# FlightControllerBoard.net
KiCad netlist of a schematic drawn in EAGLE
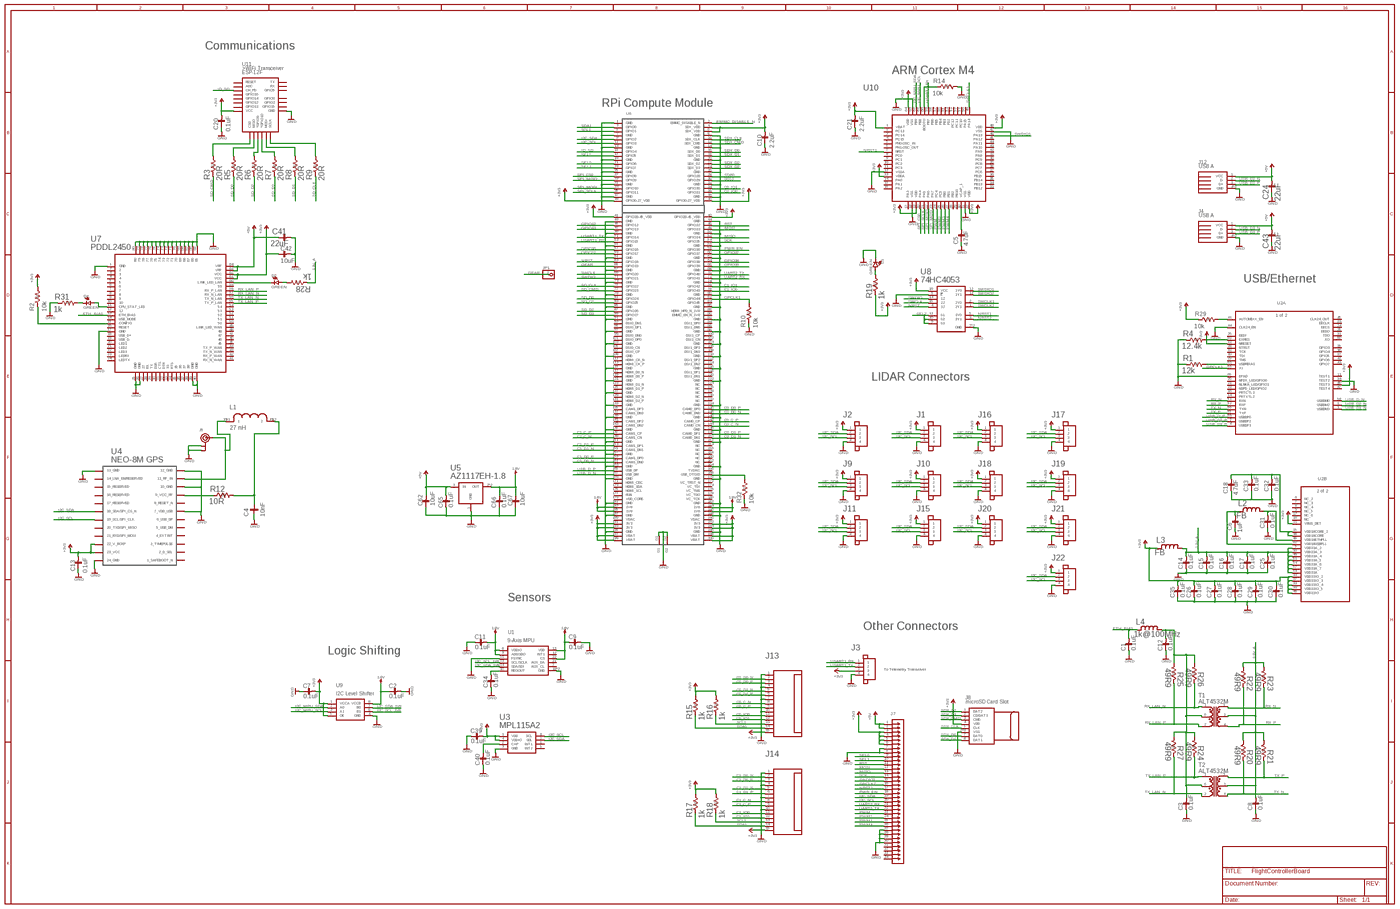
[diagram p0: schematic, sheet 1, overview]
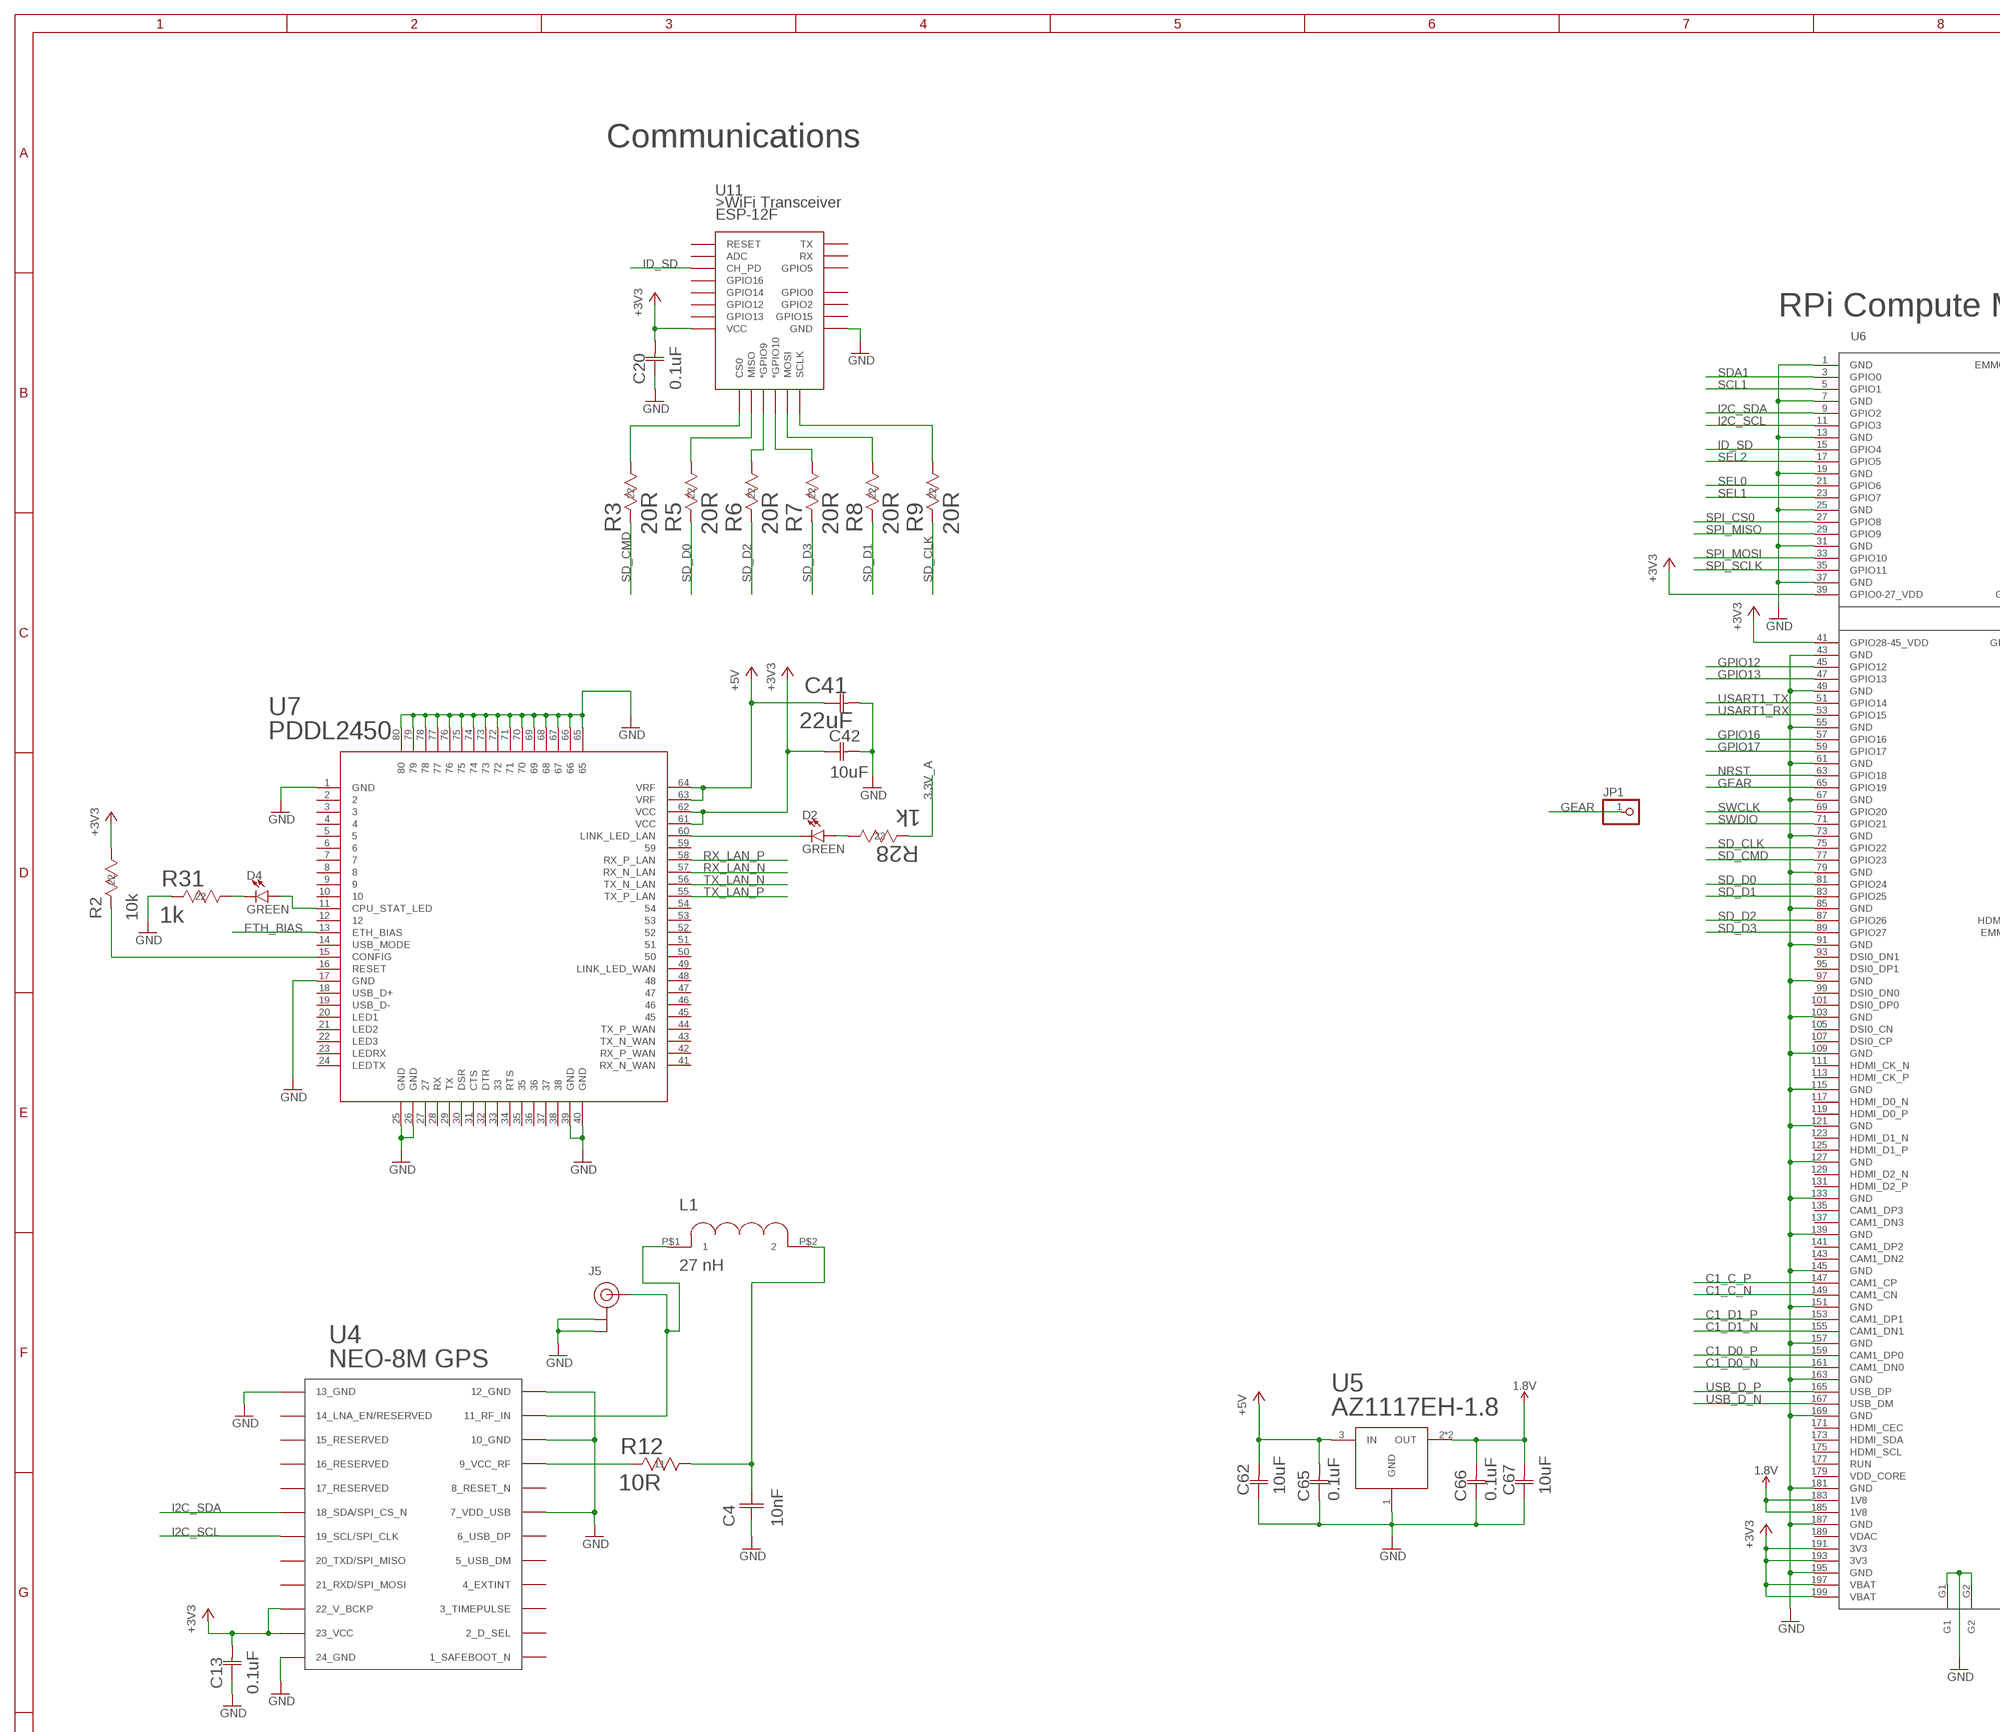
[diagram p1: schematic, sheet 1, part 1 of 4]
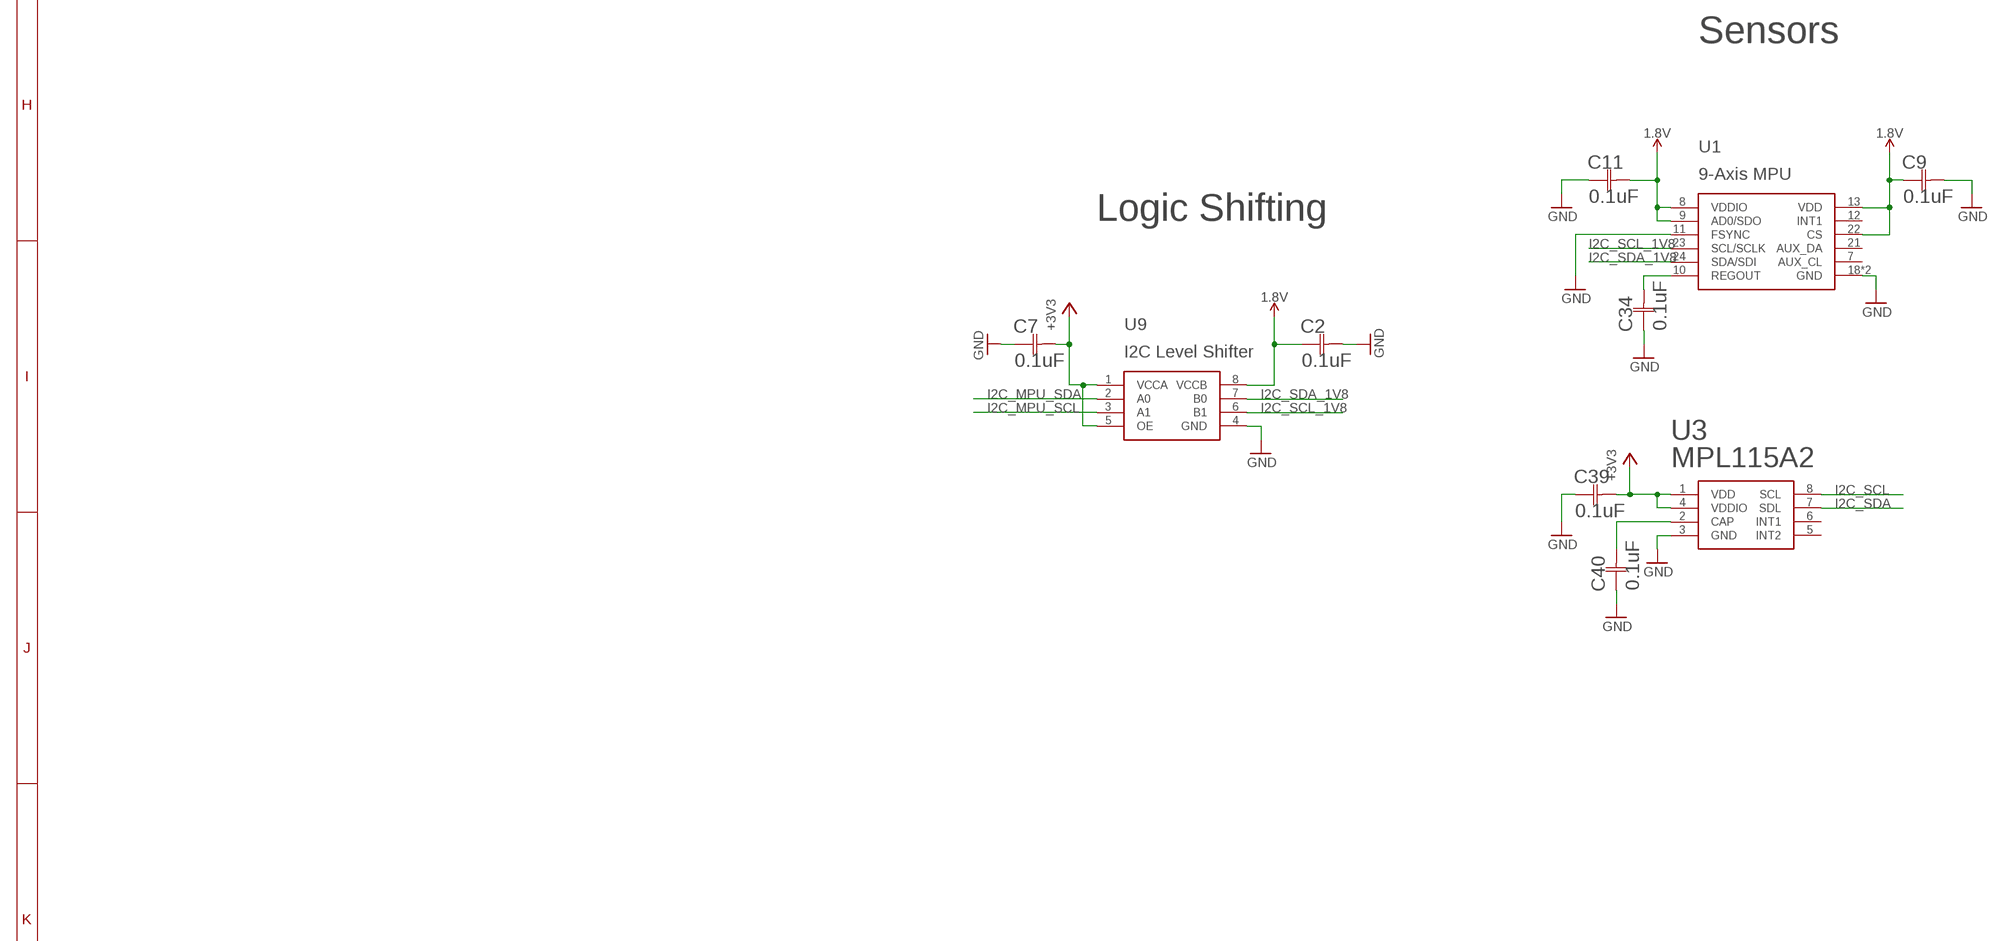
[diagram p2: schematic, sheet 1, part 2 of 4]
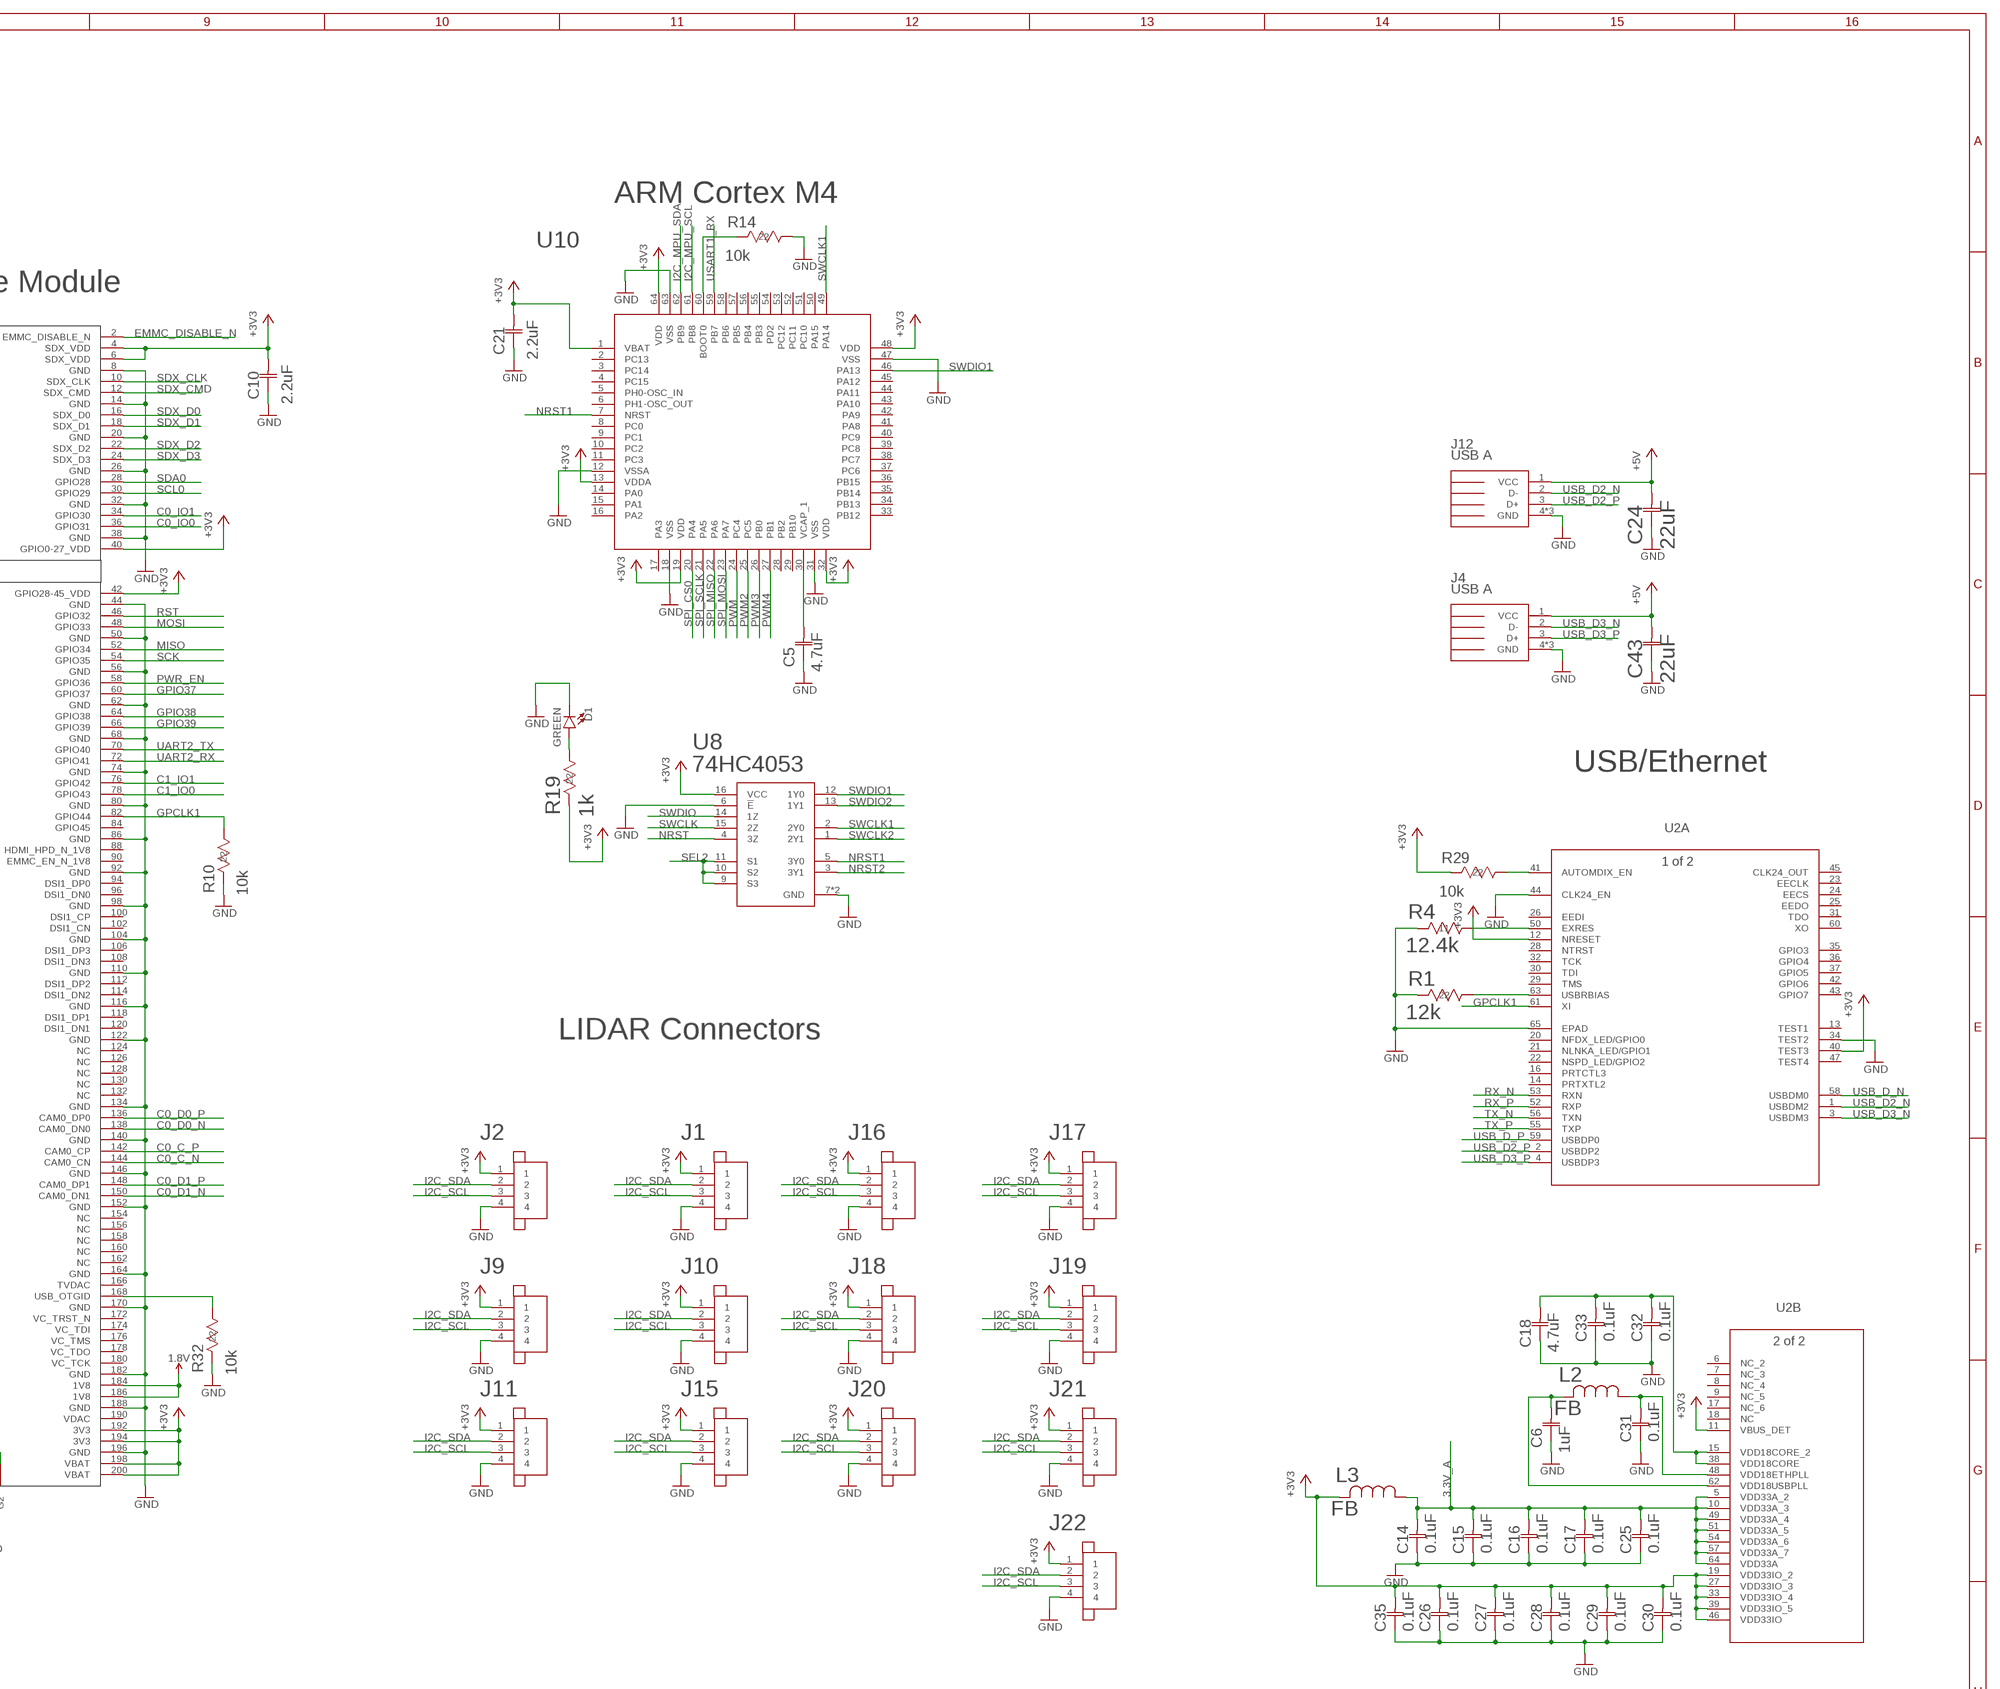
[diagram p3: schematic, sheet 1, part 3 of 4]
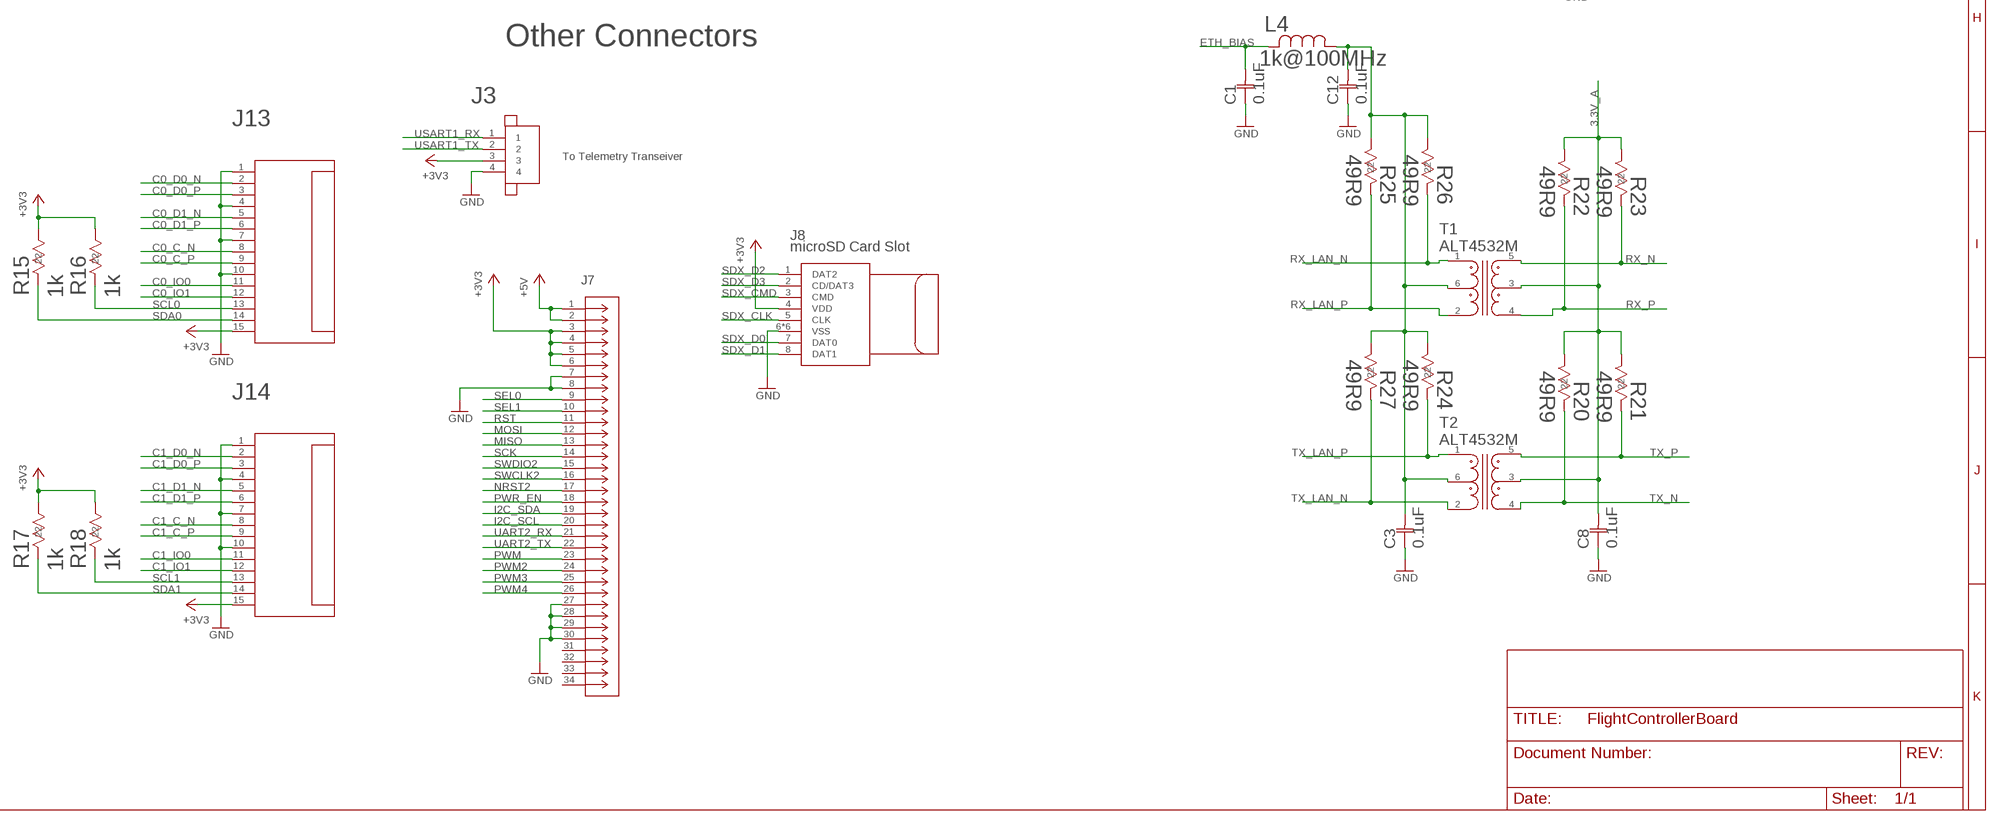
[diagram p4: schematic, sheet 1, part 4 of 4]

(export (version "E")
  (design (tool "Eeschema 10.0.6"))
  (components
    (comp (ref "C1")
      (value "0.1uF")
      (footprint "eagle-import:0402-M")
      (fields (field (name "MANUFACTURER_PART_NUMBER") "0402ZD104KAT2A"))
      (libsource (lib "eagle-import") (part "0402ZD104KAT2A0402-M"))
    )
    (comp (ref "C2")
      (value "0.1uF")
      (footprint "eagle-import:0402-M")
      (fields (field (name "MANUFACTURER_PART_NUMBER") "0402ZD104KAT2A"))
      (libsource (lib "eagle-import") (part "0402ZD104KAT2A0402-M"))
    )
    (comp (ref "C3")
      (value "0.1uF")
      (footprint "eagle-import:0402-M")
      (fields (field (name "MANUFACTURER_PART_NUMBER") "0402ZD104KAT2A"))
      (libsource (lib "eagle-import") (part "0402ZD104KAT2A0402-M"))
    )
    (comp (ref "C4")
      (value "10nF")
      (footprint "eagle-import:0603_CAPACITOR")
      (libsource (lib "eagle-import") (part "10NF_CAPACITOR"))
    )
    (comp (ref "C5")
      (value "4.7uF")
      (footprint "eagle-import:0603-M")
      (fields (field (name "MANUFACTURER_PART_NUMBER") "06036D475KAT2A"))
      (libsource (lib "eagle-import") (part "06036D475KAT2A0603-M"))
    )
    (comp (ref "C6")
      (value "1uF")
      (footprint "eagle-import:YAG_CC0805")
      (fields
        (field (name "MANUFACTURER_PART_NUMBER") "CC0805KKX7R7BB105")
        (field (name "COPYRIGHT") "Copyright C 2015 Accelerated Designs. All rights reserved")
      )
      (libsource (lib "eagle-import") (part "CC0805KKX7R7BB105"))
    )
    (comp (ref "C7")
      (value "0.1uF")
      (footprint "eagle-import:0402-M")
      (fields (field (name "MANUFACTURER_PART_NUMBER") "0402ZD104KAT2A"))
      (libsource (lib "eagle-import") (part "0402ZD104KAT2A0402-M"))
    )
    (comp (ref "C8")
      (value "0.1uF")
      (footprint "eagle-import:0402-M")
      (fields (field (name "MANUFACTURER_PART_NUMBER") "0402ZD104KAT2A"))
      (libsource (lib "eagle-import") (part "0402ZD104KAT2A0402-M"))
    )
    (comp (ref "C9")
      (value "0.1uF")
      (footprint "eagle-import:0402-M")
      (fields (field (name "MANUFACTURER_PART_NUMBER") "0402ZD104KAT2A"))
      (libsource (lib "eagle-import") (part "0402ZD104KAT2A0402-M"))
    )
    (comp (ref "C10")
      (value "2.2uF")
      (footprint "eagle-import:G-188-M")
      (fields
        (field (name "MANUFACTURER_PART_NUMBER") "GRM188R61C225KE15J")
        (field (name "COPYRIGHT") "Copyright C 2015 Accelerated Designs. All rights reserved")
      )
      (libsource (lib "eagle-import") (part "GRM188R61C225KE15JG-188-M"))
    )
    (comp (ref "C11")
      (value "0.1uF")
      (footprint "eagle-import:0402-M")
      (fields (field (name "MANUFACTURER_PART_NUMBER") "0402ZD104KAT2A"))
      (libsource (lib "eagle-import") (part "0402ZD104KAT2A0402-M"))
    )
    (comp (ref "C12")
      (value "0.1uF")
      (footprint "eagle-import:0402-M")
      (fields (field (name "MANUFACTURER_PART_NUMBER") "0402ZD104KAT2A"))
      (libsource (lib "eagle-import") (part "0402ZD104KAT2A0402-M"))
    )
    (comp (ref "C13")
      (value "0.1uF")
      (footprint "eagle-import:0805")
      (fields
        (field (name "MANUFACTURER_PART_NUMBER") "08055C104KAT2A")
        (field (name "COPYRIGHT") "Copyright C 2015 Accelerated Designs. All rights reserved")
      )
      (libsource (lib "eagle-import") (part "08055C104KAT2A"))
    )
    (comp (ref "C14")
      (value "0.1uF")
      (footprint "eagle-import:0402-M")
      (fields (field (name "MANUFACTURER_PART_NUMBER") "0402ZD104KAT2A"))
      (libsource (lib "eagle-import") (part "0402ZD104KAT2A0402-M"))
    )
    (comp (ref "C15")
      (value "0.1uF")
      (footprint "eagle-import:0402-M")
      (fields (field (name "MANUFACTURER_PART_NUMBER") "0402ZD104KAT2A"))
      (libsource (lib "eagle-import") (part "0402ZD104KAT2A0402-M"))
    )
    (comp (ref "C16")
      (value "0.1uF")
      (footprint "eagle-import:0402-M")
      (fields (field (name "MANUFACTURER_PART_NUMBER") "0402ZD104KAT2A"))
      (libsource (lib "eagle-import") (part "0402ZD104KAT2A0402-M"))
    )
    (comp (ref "C17")
      (value "0.1uF")
      (footprint "eagle-import:0402-M")
      (fields (field (name "MANUFACTURER_PART_NUMBER") "0402ZD104KAT2A"))
      (libsource (lib "eagle-import") (part "0402ZD104KAT2A0402-M"))
    )
    (comp (ref "C18")
      (value "4.7uF")
      (footprint "eagle-import:0603-M")
      (fields (field (name "MANUFACTURER_PART_NUMBER") "06036D475KAT2A"))
      (libsource (lib "eagle-import") (part "06036D475KAT2A0603-M"))
    )
    (comp (ref "C20")
      (value "0.1uF")
      (footprint "eagle-import:0805")
      (fields
        (field (name "MANUFACTURER_PART_NUMBER") "08055C104KAT2A")
        (field (name "COPYRIGHT") "Copyright C 2015 Accelerated Designs. All rights reserved")
      )
      (libsource (lib "eagle-import") (part "08055C104KAT2A"))
    )
    (comp (ref "C21")
      (value "2.2uF")
      (footprint "eagle-import:G-188-M")
      (fields
        (field (name "MANUFACTURER_PART_NUMBER") "GRM188R61C225KE15J")
        (field (name "COPYRIGHT") "Copyright C 2015 Accelerated Designs. All rights reserved")
      )
      (libsource (lib "eagle-import") (part "GRM188R61C225KE15JG-188-M"))
    )
    (comp (ref "C24")
      (value "22uF")
      (footprint "eagle-import:G-21")
      (fields
        (field (name "MANUFACTURER_PART_NUMBER") "GRM21BR60J226ME39L")
        (field (name "COPYRIGHT") "Copyright C 2015 Accelerated Designs. All rights reserved")
      )
      (libsource (lib "eagle-import") (part "GRM21BR60J226ME39L"))
    )
    (comp (ref "C25")
      (value "0.1uF")
      (footprint "eagle-import:0402-M")
      (fields (field (name "MANUFACTURER_PART_NUMBER") "0402ZD104KAT2A"))
      (libsource (lib "eagle-import") (part "0402ZD104KAT2A0402-M"))
    )
    (comp (ref "C26")
      (value "0.1uF")
      (footprint "eagle-import:0402-M")
      (fields (field (name "MANUFACTURER_PART_NUMBER") "0402ZD104KAT2A"))
      (libsource (lib "eagle-import") (part "0402ZD104KAT2A0402-M"))
    )
    (comp (ref "C27")
      (value "0.1uF")
      (footprint "eagle-import:0402-M")
      (fields (field (name "MANUFACTURER_PART_NUMBER") "0402ZD104KAT2A"))
      (libsource (lib "eagle-import") (part "0402ZD104KAT2A0402-M"))
    )
    (comp (ref "C28")
      (value "0.1uF")
      (footprint "eagle-import:0402-M")
      (fields (field (name "MANUFACTURER_PART_NUMBER") "0402ZD104KAT2A"))
      (libsource (lib "eagle-import") (part "0402ZD104KAT2A0402-M"))
    )
    (comp (ref "C29")
      (value "0.1uF")
      (footprint "eagle-import:0402-M")
      (fields (field (name "MANUFACTURER_PART_NUMBER") "0402ZD104KAT2A"))
      (libsource (lib "eagle-import") (part "0402ZD104KAT2A0402-M"))
    )
    (comp (ref "C30")
      (value "0.1uF")
      (footprint "eagle-import:0402-M")
      (fields (field (name "MANUFACTURER_PART_NUMBER") "0402ZD104KAT2A"))
      (libsource (lib "eagle-import") (part "0402ZD104KAT2A0402-M"))
    )
    (comp (ref "C31")
      (value "0.1uF")
      (footprint "eagle-import:0402-M")
      (fields (field (name "MANUFACTURER_PART_NUMBER") "0402ZD104KAT2A"))
      (libsource (lib "eagle-import") (part "0402ZD104KAT2A0402-M"))
    )
    (comp (ref "C32")
      (value "0.1uF")
      (footprint "eagle-import:0402-M")
      (fields (field (name "MANUFACTURER_PART_NUMBER") "0402ZD104KAT2A"))
      (libsource (lib "eagle-import") (part "0402ZD104KAT2A0402-M"))
    )
    (comp (ref "C33")
      (value "0.1uF")
      (footprint "eagle-import:0402-M")
      (fields (field (name "MANUFACTURER_PART_NUMBER") "0402ZD104KAT2A"))
      (libsource (lib "eagle-import") (part "0402ZD104KAT2A0402-M"))
    )
    (comp (ref "C34")
      (value "0.1uF")
      (footprint "eagle-import:0402-M")
      (fields (field (name "MANUFACTURER_PART_NUMBER") "0402ZD104KAT2A"))
      (libsource (lib "eagle-import") (part "0402ZD104KAT2A0402-M"))
    )
    (comp (ref "C35")
      (value "0.1uF")
      (footprint "eagle-import:0402-M")
      (fields (field (name "MANUFACTURER_PART_NUMBER") "0402ZD104KAT2A"))
      (libsource (lib "eagle-import") (part "0402ZD104KAT2A0402-M"))
    )
    (comp (ref "C39")
      (value "0.1uF")
      (footprint "eagle-import:0402-M")
      (fields (field (name "MANUFACTURER_PART_NUMBER") "0402ZD104KAT2A"))
      (libsource (lib "eagle-import") (part "0402ZD104KAT2A0402-M"))
    )
    (comp (ref "C40")
      (value "0.1uF")
      (footprint "eagle-import:0402-M")
      (fields (field (name "MANUFACTURER_PART_NUMBER") "0402ZD104KAT2A"))
      (libsource (lib "eagle-import") (part "0402ZD104KAT2A0402-M"))
    )
    (comp (ref "C41")
      (value "22uF")
      (footprint "eagle-import:G-21")
      (fields
        (field (name "MANUFACTURER_PART_NUMBER") "GRM21BR60J226ME39L")
        (field (name "COPYRIGHT") "Copyright C 2015 Accelerated Designs. All rights reserved")
      )
      (libsource (lib "eagle-import") (part "GRM21BR60J226ME39L"))
    )
    (comp (ref "C42")
      (value "10uF")
      (footprint "eagle-import:G-21")
      (fields
        (field (name "MANUFACTURER_PART_NUMBER") "GRM21BR60J106ME19L")
        (field (name "COPYRIGHT") "Copyright C 2015 Accelerated Designs. All rights reserved")
      )
      (libsource (lib "eagle-import") (part "GRM21BR60J106ME19L"))
    )
    (comp (ref "C43")
      (value "22uF")
      (footprint "eagle-import:G-21")
      (fields
        (field (name "MANUFACTURER_PART_NUMBER") "GRM21BR60J226ME39L")
        (field (name "COPYRIGHT") "Copyright C 2015 Accelerated Designs. All rights reserved")
      )
      (libsource (lib "eagle-import") (part "GRM21BR60J226ME39L"))
    )
    (comp (ref "C62")
      (value "10uF")
      (footprint "eagle-import:G-21")
      (fields
        (field (name "MANUFACTURER_PART_NUMBER") "GRM21BR60J106ME19L")
        (field (name "COPYRIGHT") "Copyright C 2015 Accelerated Designs. All rights reserved")
      )
      (libsource (lib "eagle-import") (part "GRM21BR60J106ME19L"))
    )
    (comp (ref "C65")
      (value "0.1uF")
      (footprint "eagle-import:0402-M")
      (fields (field (name "MANUFACTURER_PART_NUMBER") "0402ZD104KAT2A"))
      (libsource (lib "eagle-import") (part "0402ZD104KAT2A0402-M"))
    )
    (comp (ref "C66")
      (value "0.1uF")
      (footprint "eagle-import:0402-M")
      (fields (field (name "MANUFACTURER_PART_NUMBER") "0402ZD104KAT2A"))
      (libsource (lib "eagle-import") (part "0402ZD104KAT2A0402-M"))
    )
    (comp (ref "C67")
      (value "10uF")
      (footprint "eagle-import:G-21")
      (fields
        (field (name "MANUFACTURER_PART_NUMBER") "GRM21BR60J106ME19L")
        (field (name "COPYRIGHT") "Copyright C 2015 Accelerated Designs. All rights reserved")
      )
      (libsource (lib "eagle-import") (part "GRM21BR60J106ME19L"))
    )
    (comp (ref "D1")
      (value "GREEN")
      (footprint "eagle-import:LED-0603")
      (libsource (lib "eagle-import") (part "LED-GREEN0603"))
    )
    (comp (ref "D2")
      (value "GREEN")
      (footprint "eagle-import:LED-0603")
      (libsource (lib "eagle-import") (part "LED-GREEN0603"))
    )
    (comp (ref "D4")
      (value "GREEN")
      (footprint "eagle-import:LED-0603")
      (libsource (lib "eagle-import") (part "LED-GREEN0603"))
    )
    (comp (ref "J1")
      (value "JST_SH_4POS")
      (footprint "eagle-import:JST_SH_4POS")
      (libsource (lib "eagle-import") (part "JST_SH_4POS"))
    )
    (comp (ref "J2")
      (value "JST_SH_4POS")
      (footprint "eagle-import:JST_SH_4POS")
      (libsource (lib "eagle-import") (part "JST_SH_4POS"))
    )
    (comp (ref "J3")
      (value "JST_SH_4POS")
      (footprint "eagle-import:JST_SH_4POS")
      (libsource (lib "eagle-import") (part "JST_SH_4POS"))
    )
    (comp (ref "J4")
      (value "UE27AE54100")
      (footprint "eagle-import:USBA_RECEPT_VERT")
      (libsource (lib "eagle-import") (part "UE27AE54100"))
    )
    (comp (ref "J5")
      (value "U.FL")
      (footprint "eagle-import:U.FL")
      (libsource (lib "eagle-import") (part "U.FL"))
    )
    (comp (ref "J7")
      (value "62674-301121ALF")
      (footprint "eagle-import:CON30_1X30_DUT_58XF")
      (fields (field (name "MANUFACTURER_PART_NUMBER") "62674301121ALF"))
      (libsource (lib "eagle-import") (part "62674-301121ALF"))
    )
    (comp (ref "J8")
      (value "MICROSD")
      (footprint "eagle-import:MICROSD")
      (libsource (lib "eagle-import") (part "MICROSD"))
    )
    (comp (ref "J9")
      (value "JST_SH_4POS")
      (footprint "eagle-import:JST_SH_4POS")
      (libsource (lib "eagle-import") (part "JST_SH_4POS"))
    )
    (comp (ref "J10")
      (value "JST_SH_4POS")
      (footprint "eagle-import:JST_SH_4POS")
      (libsource (lib "eagle-import") (part "JST_SH_4POS"))
    )
    (comp (ref "J11")
      (value "JST_SH_4POS")
      (footprint "eagle-import:JST_SH_4POS")
      (libsource (lib "eagle-import") (part "JST_SH_4POS"))
    )
    (comp (ref "J12")
      (value "UE27AE54100")
      (footprint "eagle-import:USBA_RECEPT_VERT")
      (libsource (lib "eagle-import") (part "UE27AE54100"))
    )
    (comp (ref "J13")
      (value "0526101572_15ZIF_CONNECTOR")
      (footprint "eagle-import:15POS_FFC_CONNECTOR")
      (libsource (lib "eagle-import") (part "0526101572_15ZIF_CONNECTOR"))
    )
    (comp (ref "J14")
      (value "0526101572_15ZIF_CONNECTOR")
      (footprint "eagle-import:15POS_FFC_CONNECTOR")
      (libsource (lib "eagle-import") (part "0526101572_15ZIF_CONNECTOR"))
    )
    (comp (ref "J15")
      (value "JST_SH_4POS")
      (footprint "eagle-import:JST_SH_4POS")
      (libsource (lib "eagle-import") (part "JST_SH_4POS"))
    )
    (comp (ref "J16")
      (value "JST_SH_4POS")
      (footprint "eagle-import:JST_SH_4POS")
      (libsource (lib "eagle-import") (part "JST_SH_4POS"))
    )
    (comp (ref "J17")
      (value "JST_SH_4POS")
      (footprint "eagle-import:JST_SH_4POS")
      (libsource (lib "eagle-import") (part "JST_SH_4POS"))
    )
    (comp (ref "J18")
      (value "JST_SH_4POS")
      (footprint "eagle-import:JST_SH_4POS")
      (libsource (lib "eagle-import") (part "JST_SH_4POS"))
    )
    (comp (ref "J19")
      (value "JST_SH_4POS")
      (footprint "eagle-import:JST_SH_4POS")
      (libsource (lib "eagle-import") (part "JST_SH_4POS"))
    )
    (comp (ref "J20")
      (value "JST_SH_4POS")
      (footprint "eagle-import:JST_SH_4POS")
      (libsource (lib "eagle-import") (part "JST_SH_4POS"))
    )
    (comp (ref "J21")
      (value "JST_SH_4POS")
      (footprint "eagle-import:JST_SH_4POS")
      (libsource (lib "eagle-import") (part "JST_SH_4POS"))
    )
    (comp (ref "J22")
      (value "JST_SH_4POS")
      (footprint "eagle-import:JST_SH_4POS")
      (libsource (lib "eagle-import") (part "JST_SH_4POS"))
    )
    (comp (ref "JP1")
      (value "PINHD-1X1")
      (footprint "eagle-import:1X01")
      (libsource (lib "eagle-import") (part "PINHD-1X1"))
    )
    (comp (ref "L1")
      (value "27 nH")
      (footprint "eagle-import:0402_INDUCTOR")
      (libsource (lib "eagle-import") (part "27NH_INDUCTOR"))
    )
    (comp (ref "L2")
      (value "FB")
      (footprint "eagle-import:IND_BLM18_0603-M")
      (fields (field (name "MANUFACTURER_PART_NUMBER") "BLM18AG601SN1D"))
      (libsource (lib "eagle-import") (part "BLM18AG601SN1DIND_BLM18_0603-M"))
    )
    (comp (ref "L3")
      (value "FB")
      (footprint "eagle-import:IND_BLM18_0603-M")
      (fields (field (name "MANUFACTURER_PART_NUMBER") "BLM18AG601SN1D"))
      (libsource (lib "eagle-import") (part "BLM18AG601SN1DIND_BLM18_0603-M"))
    )
    (comp (ref "L4")
      (value "1k@100MHz")
      (footprint "eagle-import:IND_BLM18_0603-M")
      (fields (field (name "MANUFACTURER_PART_NUMBER") "BLM18AG601SN1D"))
      (libsource (lib "eagle-import") (part "BLM18AG601SN1DIND_BLM18_0603-M"))
    )
    (comp (ref "R1")
      (value "12k")
      (footprint "eagle-import:RC0402N-M")
      (fields (field (name "MANUFACTURER_PART_NUMBER") "RC0402FR0712KL"))
      (libsource (lib "eagle-import") (part "RC0402FR-0712KLRC0402N-M"))
    )
    (comp (ref "R2")
      (value "10k")
      (footprint "eagle-import:RC0603N-M")
      (fields (field (name "MANUFACTURER_PART_NUMBER") "RC0603JR0710KL"))
      (libsource (lib "eagle-import") (part "RC0603JR-0710KLRC0603N-M"))
    )
    (comp (ref "R3")
      (value "20R")
      (footprint "eagle-import:RC0603N-M")
      (fields (field (name "MANUFACTURER_PART_NUMBER") "RC0603JR0720RL"))
      (libsource (lib "eagle-import") (part "RC0603JR-0720RLRC0603N-M"))
    )
    (comp (ref "R4")
      (value "12.4k")
      (footprint "eagle-import:YAG_R0402-M")
      (fields (field (name "MANUFACTURER_PART_NUMBER") "RC0402FR0712K4L"))
      (libsource (lib "eagle-import") (part "RC0402FR-0712K4LYAG_R0402-M"))
    )
    (comp (ref "R5")
      (value "20R")
      (footprint "eagle-import:RC0603N-M")
      (fields (field (name "MANUFACTURER_PART_NUMBER") "RC0603JR0720RL"))
      (libsource (lib "eagle-import") (part "RC0603JR-0720RLRC0603N-M"))
    )
    (comp (ref "R6")
      (value "20R")
      (footprint "eagle-import:RC0603N-M")
      (fields (field (name "MANUFACTURER_PART_NUMBER") "RC0603JR0720RL"))
      (libsource (lib "eagle-import") (part "RC0603JR-0720RLRC0603N-M"))
    )
    (comp (ref "R7")
      (value "20R")
      (footprint "eagle-import:RC0603N-M")
      (fields (field (name "MANUFACTURER_PART_NUMBER") "RC0603JR0720RL"))
      (libsource (lib "eagle-import") (part "RC0603JR-0720RLRC0603N-M"))
    )
    (comp (ref "R8")
      (value "20R")
      (footprint "eagle-import:RC0603N-M")
      (fields (field (name "MANUFACTURER_PART_NUMBER") "RC0603JR0720RL"))
      (libsource (lib "eagle-import") (part "RC0603JR-0720RLRC0603N-M"))
    )
    (comp (ref "R9")
      (value "20R")
      (footprint "eagle-import:RC0603N-M")
      (fields (field (name "MANUFACTURER_PART_NUMBER") "RC0603JR0720RL"))
      (libsource (lib "eagle-import") (part "RC0603JR-0720RLRC0603N-M"))
    )
    (comp (ref "R10")
      (value "10k")
      (footprint "eagle-import:RC0603N-M")
      (fields (field (name "MANUFACTURER_PART_NUMBER") "RC0603JR0710KL"))
      (libsource (lib "eagle-import") (part "RC0603JR-0710KLRC0603N-M"))
    )
    (comp (ref "R12")
      (value "10R")
      (footprint "eagle-import:STA_RNCP0805-M")
      (fields
        (field (name "MANUFACTURER_PART_NUMBER") "RNCP0805FTD10R0")
        (field (name "COPYRIGHT") "Copyright C 2015 Accelerated Designs. All rights reserved")
      )
      (libsource (lib "eagle-import") (part "RNCP0805FTD10R0STA_RNCP0805-M"))
    )
    (comp (ref "R14")
      (value "10k")
      (footprint "eagle-import:RC0603N-M")
      (fields (field (name "MANUFACTURER_PART_NUMBER") "RC0603JR0710KL"))
      (libsource (lib "eagle-import") (part "RC0603JR-0710KLRC0603N-M"))
    )
    (comp (ref "R15")
      (value "1k")
      (footprint "eagle-import:RC0603N-M")
      (fields
        (field (name "DIGIKEYPARTNUMBER") "3111.0KGRTRND")
        (field (name "MANUFACTURER_PART_NUMBER") "RC0603JR071KL")
        (field (name "NEWARKPARTNUMBER") "14M7231")
        (field (name "COPYRIGHT") "Copyright C 2015 Accelerated Designs. All rights reserved")
      )
      (libsource (lib "eagle-import") (part "RC0603JR-071KLRC0603N-M"))
    )
    (comp (ref "R16")
      (value "1k")
      (footprint "eagle-import:RC0603N-M")
      (fields
        (field (name "DIGIKEYPARTNUMBER") "3111.0KGRTRND")
        (field (name "MANUFACTURER_PART_NUMBER") "RC0603JR071KL")
        (field (name "NEWARKPARTNUMBER") "14M7231")
        (field (name "COPYRIGHT") "Copyright C 2015 Accelerated Designs. All rights reserved")
      )
      (libsource (lib "eagle-import") (part "RC0603JR-071KLRC0603N-M"))
    )
    (comp (ref "R17")
      (value "1k")
      (footprint "eagle-import:RC0603N-M")
      (fields
        (field (name "DIGIKEYPARTNUMBER") "3111.0KGRTRND")
        (field (name "MANUFACTURER_PART_NUMBER") "RC0603JR071KL")
        (field (name "NEWARKPARTNUMBER") "14M7231")
        (field (name "COPYRIGHT") "Copyright C 2015 Accelerated Designs. All rights reserved")
      )
      (libsource (lib "eagle-import") (part "RC0603JR-071KLRC0603N-M"))
    )
    (comp (ref "R18")
      (value "1k")
      (footprint "eagle-import:RC0603N-M")
      (fields
        (field (name "DIGIKEYPARTNUMBER") "3111.0KGRTRND")
        (field (name "MANUFACTURER_PART_NUMBER") "RC0603JR071KL")
        (field (name "NEWARKPARTNUMBER") "14M7231")
        (field (name "COPYRIGHT") "Copyright C 2015 Accelerated Designs. All rights reserved")
      )
      (libsource (lib "eagle-import") (part "RC0603JR-071KLRC0603N-M"))
    )
    (comp (ref "R19")
      (value "1k")
      (footprint "eagle-import:RC0603N-M")
      (fields
        (field (name "DIGIKEYPARTNUMBER") "3111.0KGRTRND")
        (field (name "MANUFACTURER_PART_NUMBER") "RC0603JR071KL")
        (field (name "NEWARKPARTNUMBER") "14M7231")
        (field (name "COPYRIGHT") "Copyright C 2015 Accelerated Designs. All rights reserved")
      )
      (libsource (lib "eagle-import") (part "RC0603JR-071KLRC0603N-M"))
    )
    (comp (ref "R20")
      (value "49R9")
      (footprint "eagle-import:RC0402N-M")
      (fields (field (name "MANUFACTURER_PART_NUMBER") "RC0402FR0749K9L"))
      (libsource (lib "eagle-import") (part "RC0402FR-0749K9LRC0402N-M"))
    )
    (comp (ref "R21")
      (value "49R9")
      (footprint "eagle-import:RC0402N-M")
      (fields (field (name "MANUFACTURER_PART_NUMBER") "RC0402FR0749K9L"))
      (libsource (lib "eagle-import") (part "RC0402FR-0749K9LRC0402N-M"))
    )
    (comp (ref "R22")
      (value "49R9")
      (footprint "eagle-import:RC0402N-M")
      (fields (field (name "MANUFACTURER_PART_NUMBER") "RC0402FR0749K9L"))
      (libsource (lib "eagle-import") (part "RC0402FR-0749K9LRC0402N-M"))
    )
    (comp (ref "R23")
      (value "49R9")
      (footprint "eagle-import:RC0402N-M")
      (fields (field (name "MANUFACTURER_PART_NUMBER") "RC0402FR0749K9L"))
      (libsource (lib "eagle-import") (part "RC0402FR-0749K9LRC0402N-M"))
    )
    (comp (ref "R24")
      (value "49R9")
      (footprint "eagle-import:RC0402N-M")
      (fields (field (name "MANUFACTURER_PART_NUMBER") "RC0402FR0749K9L"))
      (libsource (lib "eagle-import") (part "RC0402FR-0749K9LRC0402N-M"))
    )
    (comp (ref "R25")
      (value "49R9")
      (footprint "eagle-import:RC0402N-M")
      (fields (field (name "MANUFACTURER_PART_NUMBER") "RC0402FR0749K9L"))
      (libsource (lib "eagle-import") (part "RC0402FR-0749K9LRC0402N-M"))
    )
    (comp (ref "R26")
      (value "49R9")
      (footprint "eagle-import:RC0402N-M")
      (fields (field (name "MANUFACTURER_PART_NUMBER") "RC0402FR0749K9L"))
      (libsource (lib "eagle-import") (part "RC0402FR-0749K9LRC0402N-M"))
    )
    (comp (ref "R27")
      (value "49R9")
      (footprint "eagle-import:RC0402N-M")
      (fields (field (name "MANUFACTURER_PART_NUMBER") "RC0402FR0749K9L"))
      (libsource (lib "eagle-import") (part "RC0402FR-0749K9LRC0402N-M"))
    )
    (comp (ref "R28")
      (value "1k")
      (footprint "eagle-import:RC0603N-M")
      (fields
        (field (name "DIGIKEYPARTNUMBER") "3111.0KGRTRND")
        (field (name "MANUFACTURER_PART_NUMBER") "RC0603JR071KL")
        (field (name "NEWARKPARTNUMBER") "14M7231")
        (field (name "COPYRIGHT") "Copyright C 2015 Accelerated Designs. All rights reserved")
      )
      (libsource (lib "eagle-import") (part "RC0603JR-071KLRC0603N-M"))
    )
    (comp (ref "R29")
      (value "10k")
      (footprint "eagle-import:RC0603N-M")
      (fields (field (name "MANUFACTURER_PART_NUMBER") "RC0603JR0710KL"))
      (libsource (lib "eagle-import") (part "RC0603JR-0710KLRC0603N-M"))
    )
    (comp (ref "R31")
      (value "1k")
      (footprint "eagle-import:RC0603N-M")
      (fields
        (field (name "DIGIKEYPARTNUMBER") "3111.0KGRTRND")
        (field (name "MANUFACTURER_PART_NUMBER") "RC0603JR071KL")
        (field (name "NEWARKPARTNUMBER") "14M7231")
        (field (name "COPYRIGHT") "Copyright C 2015 Accelerated Designs. All rights reserved")
      )
      (libsource (lib "eagle-import") (part "RC0603JR-071KLRC0603N-M"))
    )
    (comp (ref "R32")
      (value "10k")
      (footprint "eagle-import:RC0603N-M")
      (fields (field (name "MANUFACTURER_PART_NUMBER") "RC0603JR0710KL"))
      (libsource (lib "eagle-import") (part "RC0603JR-0710KLRC0603N-M"))
    )
    (comp (ref "T1")
      (value "ALT4532M")
      (footprint "eagle-import:ALT4532")
      (libsource (lib "eagle-import") (part "ALT4532M"))
    )
    (comp (ref "T2")
      (value "ALT4532M")
      (footprint "eagle-import:ALT4532")
      (libsource (lib "eagle-import") (part "ALT4532M"))
    )
    (comp (ref "U1")
      (value "ICM-20948")
      (footprint "eagle-import:QFN40P300X300X105-25N")
      (libsource (lib "eagle-import") (part "ICM-20948"))
    )
    (comp (ref "U2")
      (value "LAN9512-JZXQFN64_9X9MC-M")
      (footprint "eagle-import:QFN64_9X9MC-M")
      (fields (field (name "MANUFACTURER_PART_NUMBER") "LAN9512JZX"))
      (libsource (lib "eagle-import") (part "LAN9512-JZXQFN64_9X9MC-M"))
    )
    (comp (ref "U3")
      (value "MPL115A2")
      (footprint "eagle-import:LGA8-M")
      (libsource (lib "eagle-import") (part "MPL115A2"))
    )
    (comp (ref "U4")
      (value "NEO-M8")
      (footprint "eagle-import:NEO-M8")
      (libsource (lib "eagle-import") (part "NEO-M8"))
    )
    (comp (ref "U5")
      (value "AZ1117EH-1.8")
      (footprint "eagle-import:SOT-223")
      (libsource (lib "eagle-import") (part "AZ1117EH-1.8"))
    )
    (comp (ref "U6")
      (value "COMPUTE_MODULE")
      (footprint "eagle-import:SO-DIMM")
      (libsource (lib "eagle-import") (part "COMPUTE_MODULE"))
    )
    (comp (ref "U7")
      (value "PDDL2450")
      (footprint "eagle-import:PDDL2450_SOCKET")
      (libsource (lib "eagle-import") (part "PDDL2450"))
    )
    (comp (ref "U8")
      (value "74HC4053")
      (footprint "eagle-import:TSSOP16")
      (libsource (lib "eagle-import") (part "74HC4053"))
    )
    (comp (ref "U9")
      (value "FXMAR2102")
      (footprint "eagle-import:8-UMLP")
      (libsource (lib "eagle-import") (part "FXMAR2102"))
    )
    (comp (ref "U10")
      (value "STM32F446")
      (footprint "eagle-import:LQFP64")
      (libsource (lib "eagle-import") (part "STM32F446"))
    )
    (comp (ref "U11")
      (value "ESP12ESMD")
      (footprint "eagle-import:ESP12E-SMD")
      (libsource (lib "eagle-import") (part "ESP12ESMD"))
    )
  )
  (nets
    (net (code "1") (name "+3V3") (class "Default")
      (node (ref "C10") (pin "2") (pinfunction "22_2") (pintype "passive"))
      (node (ref "C13") (pin "2") (pinfunction "2_2") (pintype "passive"))
      (node (ref "C20") (pin "2") (pinfunction "2_2") (pintype "passive"))
      (node (ref "C21") (pin "2") (pinfunction "22_2") (pintype "passive"))
      (node (ref "C26") (pin "2") (pinfunction "2_2") (pintype "passive"))
      (node (ref "C27") (pin "2") (pinfunction "2_2") (pintype "passive"))
      (node (ref "C28") (pin "2") (pinfunction "2_2") (pintype "passive"))
      (node (ref "C29") (pin "2") (pinfunction "2_2") (pintype "passive"))
      (node (ref "C30") (pin "2") (pinfunction "2_2") (pintype "passive"))
      (node (ref "C35") (pin "2") (pinfunction "2_2") (pintype "passive"))
      (node (ref "C39") (pin "2") (pinfunction "2_2") (pintype "passive"))
      (node (ref "C42") (pin "1") (pinfunction "11_1") (pintype "passive"))
      (node (ref "C7") (pin "2") (pinfunction "2_2") (pintype "passive"))
      (node (ref "J1") (pin "1") (pinfunction "1_1") (pintype "bidirectional"))
      (node (ref "J10") (pin "1") (pinfunction "1_1") (pintype "bidirectional"))
      (node (ref "J11") (pin "1") (pinfunction "1_1") (pintype "bidirectional"))
      (node (ref "J13") (pin "15") (pinfunction "15_15") (pintype "bidirectional"))
      (node (ref "J14") (pin "15") (pinfunction "15_15") (pintype "bidirectional"))
      (node (ref "J15") (pin "1") (pinfunction "1_1") (pintype "bidirectional"))
      (node (ref "J16") (pin "1") (pinfunction "1_1") (pintype "bidirectional"))
      (node (ref "J17") (pin "1") (pinfunction "1_1") (pintype "bidirectional"))
      (node (ref "J18") (pin "1") (pinfunction "1_1") (pintype "bidirectional"))
      (node (ref "J19") (pin "1") (pinfunction "1_1") (pintype "bidirectional"))
      (node (ref "J2") (pin "1") (pinfunction "1_1") (pintype "bidirectional"))
      (node (ref "J20") (pin "1") (pinfunction "1_1") (pintype "bidirectional"))
      (node (ref "J21") (pin "1") (pinfunction "1_1") (pintype "bidirectional"))
      (node (ref "J22") (pin "1") (pinfunction "1_1") (pintype "bidirectional"))
      (node (ref "J3") (pin "3") (pinfunction "3_3") (pintype "bidirectional"))
      (node (ref "J7") (pin "3") (pinfunction "33_3") (pintype "passive"))
      (node (ref "J7") (pin "4") (pinfunction "44_4") (pintype "passive"))
      (node (ref "J7") (pin "5") (pinfunction "55_5") (pintype "passive"))
      (node (ref "J7") (pin "6") (pinfunction "66_6") (pintype "passive"))
      (node (ref "J8") (pin "4") (pinfunction "VDD_4") (pintype "bidirectional"))
      (node (ref "J9") (pin "1") (pinfunction "1_1") (pintype "bidirectional"))
      (node (ref "L3") (pin "2") (pinfunction "2_2") (pintype "passive"))
      (node (ref "R15") (pin "1") (pinfunction "11_1") (pintype "passive"))
      (node (ref "R16") (pin "1") (pinfunction "11_1") (pintype "passive"))
      (node (ref "R17") (pin "1") (pinfunction "11_1") (pintype "passive"))
      (node (ref "R18") (pin "1") (pinfunction "11_1") (pintype "passive"))
      (node (ref "R19") (pin "2") (pinfunction "22_2") (pintype "passive"))
      (node (ref "R2") (pin "1") (pinfunction "11_1") (pintype "passive"))
      (node (ref "R29") (pin "2") (pinfunction "22_2") (pintype "passive"))
      (node (ref "U10") (pin "1") (pinfunction "VBAT_1") (pintype "bidirectional"))
      (node (ref "U10") (pin "13") (pinfunction "VDDA_13") (pintype "bidirectional"))
      (node (ref "U10") (pin "19") (pinfunction "VDD_19") (pintype "bidirectional"))
      (node (ref "U10") (pin "32") (pinfunction "VDD_32") (pintype "bidirectional"))
      (node (ref "U10") (pin "48") (pinfunction "VDD_48") (pintype "bidirectional"))
      (node (ref "U10") (pin "64") (pinfunction "VDD_64") (pintype "bidirectional"))
      (node (ref "U11") (pin "VCC") (pinfunction "VCC_VCC") (pintype "bidirectional"))
      (node (ref "U2") (pin "11") (pinfunction "VBUS_DET_11") (pintype "power_in"))
      (node (ref "U2") (pin "12") (pinfunction "NRESET_12") (pintype "input"))
      (node (ref "U2") (pin "19") (pinfunction "VDD33IO_2_19") (pintype "power_in"))
      (node (ref "U2") (pin "27") (pinfunction "VDD33IO_3_27") (pintype "power_in"))
      (node (ref "U2") (pin "33") (pinfunction "VDD33IO_4_33") (pintype "power_in"))
      (node (ref "U2") (pin "39") (pinfunction "VDD33IO_5_39") (pintype "power_in"))
      (node (ref "U2") (pin "40") (pinfunction "TEST3_40") (pintype "passive"))
      (node (ref "U2") (pin "46") (pinfunction "VDD33IO_46") (pintype "power_in"))
      (node (ref "U3") (pin "1") (pinfunction "VDD_1") (pintype "bidirectional"))
      (node (ref "U3") (pin "4") (pinfunction "VDDIO_4") (pintype "bidirectional"))
      (node (ref "U4") (pin "22") (pinfunction "22_V_BCKP_22") (pintype "bidirectional"))
      (node (ref "U4") (pin "23") (pinfunction "23_VCC_23") (pintype "bidirectional"))
      (node (ref "U6") (pin "191") (pinfunction "3V3_191") (pintype "bidirectional"))
      (node (ref "U6") (pin "192") (pinfunction "3V3_192") (pintype "bidirectional"))
      (node (ref "U6") (pin "193") (pinfunction "3V3_193") (pintype "bidirectional"))
      (node (ref "U6") (pin "194") (pinfunction "3V3_194") (pintype "bidirectional"))
      (node (ref "U6") (pin "197") (pinfunction "VBAT_197") (pintype "bidirectional"))
      (node (ref "U6") (pin "198") (pinfunction "VBAT_198") (pintype "bidirectional"))
      (node (ref "U6") (pin "199") (pinfunction "VBAT_199") (pintype "bidirectional"))
      (node (ref "U6") (pin "200") (pinfunction "VBAT_200") (pintype "bidirectional"))
      (node (ref "U6") (pin "39") (pinfunction "GPIO0-27_VDD_39") (pintype "bidirectional"))
      (node (ref "U6") (pin "4") (pinfunction "SDX_VDD_4") (pintype "bidirectional"))
      (node (ref "U6") (pin "40") (pinfunction "GPIO0-27_VDD_40") (pintype "bidirectional"))
      (node (ref "U6") (pin "41") (pinfunction "GPIO28-45_VDD_41") (pintype "bidirectional"))
      (node (ref "U6") (pin "42") (pinfunction "GPIO28-45_VDD_42") (pintype "bidirectional"))
      (node (ref "U6") (pin "6") (pinfunction "SDX_VDD_6") (pintype "bidirectional"))
      (node (ref "U7") (pin "61") (pinfunction "VCC_61") (pintype "bidirectional"))
      (node (ref "U7") (pin "62") (pinfunction "VCC_62") (pintype "bidirectional"))
      (node (ref "U8") (pin "16") (pinfunction "VCC_16") (pintype "bidirectional"))
      (node (ref "U9") (pin "1") (pinfunction "VCCA_1") (pintype "bidirectional"))
      (node (ref "U9") (pin "5") (pinfunction "OE_5") (pintype "bidirectional"))
    )
    (net (code "2") (name "+5V") (class "Default")
      (node (ref "C24") (pin "2") (pinfunction "22_2") (pintype "passive"))
      (node (ref "C41") (pin "1") (pinfunction "11_1") (pintype "passive"))
      (node (ref "C43") (pin "2") (pinfunction "22_2") (pintype "passive"))
      (node (ref "C62") (pin "2") (pinfunction "22_2") (pintype "passive"))
      (node (ref "C65") (pin "2") (pinfunction "2_2") (pintype "passive"))
      (node (ref "J12") (pin "1") (pinfunction "VCC_1") (pintype "bidirectional"))
      (node (ref "J4") (pin "1") (pinfunction "VCC_1") (pintype "bidirectional"))
      (node (ref "J7") (pin "1") (pinfunction "11_1") (pintype "passive"))
      (node (ref "J7") (pin "2") (pinfunction "22_2") (pintype "passive"))
      (node (ref "U5") (pin "3") (pinfunction "IN_3") (pintype "bidirectional"))
      (node (ref "U7") (pin "63") (pinfunction "VRF_63") (pintype "bidirectional"))
      (node (ref "U7") (pin "64") (pinfunction "VRF_64") (pintype "bidirectional"))
    )
    (net (code "3") (name "/3.3V_A") (class "Default")
      (node (ref "C14") (pin "2") (pinfunction "2_2") (pintype "passive"))
      (node (ref "C15") (pin "2") (pinfunction "2_2") (pintype "passive"))
      (node (ref "C16") (pin "2") (pinfunction "2_2") (pintype "passive"))
      (node (ref "C17") (pin "2") (pinfunction "2_2") (pintype "passive"))
      (node (ref "C25") (pin "2") (pinfunction "2_2") (pintype "passive"))
      (node (ref "C8") (pin "2") (pinfunction "2_2") (pintype "passive"))
      (node (ref "L3") (pin "1") (pinfunction "1_1") (pintype "passive"))
      (node (ref "R20") (pin "1") (pinfunction "11_1") (pintype "passive"))
      (node (ref "R21") (pin "1") (pinfunction "11_1") (pintype "passive"))
      (node (ref "R22") (pin "1") (pinfunction "11_1") (pintype "passive"))
      (node (ref "R23") (pin "1") (pinfunction "11_1") (pintype "passive"))
      (node (ref "R28") (pin "2") (pinfunction "22_2") (pintype "passive"))
      (node (ref "T1") (pin "3") (pinfunction "3_3") (pintype "bidirectional"))
      (node (ref "T2") (pin "3") (pinfunction "3_3") (pintype "bidirectional"))
      (node (ref "U2") (pin "10") (pinfunction "VDD33A_3_10") (pintype "power_in"))
      (node (ref "U2") (pin "49") (pinfunction "VDD33A_4_49") (pintype "power_in"))
      (node (ref "U2") (pin "5") (pinfunction "VDD33A_2_5") (pintype "power_in"))
      (node (ref "U2") (pin "51") (pinfunction "VDD33A_5_51") (pintype "power_in"))
      (node (ref "U2") (pin "54") (pinfunction "VDD33A_6_54") (pintype "power_in"))
      (node (ref "U2") (pin "57") (pinfunction "VDD33A_7_57") (pintype "power_in"))
      (node (ref "U2") (pin "64") (pinfunction "VDD33A_64") (pintype "power_in"))
    )
    (net (code "4") (name "/C0_C_N") (class "Default")
      (node (ref "J13") (pin "8") (pinfunction "8_8") (pintype "bidirectional"))
      (node (ref "U6") (pin "144") (pinfunction "CAM0_CN_144") (pintype "bidirectional"))
    )
    (net (code "5") (name "/C0_C_P") (class "Default")
      (node (ref "J13") (pin "9") (pinfunction "9_9") (pintype "bidirectional"))
      (node (ref "U6") (pin "142") (pinfunction "CAM0_CP_142") (pintype "bidirectional"))
    )
    (net (code "6") (name "/C0_D0_N") (class "Default")
      (node (ref "J13") (pin "2") (pinfunction "2_2") (pintype "bidirectional"))
      (node (ref "U6") (pin "138") (pinfunction "CAM0_DN0_138") (pintype "bidirectional"))
    )
    (net (code "7") (name "/C0_D0_P") (class "Default")
      (node (ref "J13") (pin "3") (pinfunction "3_3") (pintype "bidirectional"))
      (node (ref "U6") (pin "136") (pinfunction "CAM0_DP0_136") (pintype "bidirectional"))
    )
    (net (code "8") (name "/C0_D1_N") (class "Default")
      (node (ref "J13") (pin "5") (pinfunction "5_5") (pintype "bidirectional"))
      (node (ref "U6") (pin "150") (pinfunction "CAM0_DN1_150") (pintype "bidirectional"))
    )
    (net (code "9") (name "/C0_D1_P") (class "Default")
      (node (ref "J13") (pin "6") (pinfunction "6_6") (pintype "bidirectional"))
      (node (ref "U6") (pin "148") (pinfunction "CAM0_DP1_148") (pintype "bidirectional"))
    )
    (net (code "10") (name "/C0_IO0") (class "Default")
      (node (ref "J13") (pin "11") (pinfunction "11_11") (pintype "bidirectional"))
      (node (ref "U6") (pin "36") (pinfunction "GPIO31_36") (pintype "bidirectional"))
    )
    (net (code "11") (name "/C0_IO1") (class "Default")
      (node (ref "J13") (pin "12") (pinfunction "12_12") (pintype "bidirectional"))
      (node (ref "U6") (pin "34") (pinfunction "GPIO30_34") (pintype "bidirectional"))
    )
    (net (code "12") (name "/C1_C_N") (class "Default")
      (node (ref "J14") (pin "8") (pinfunction "8_8") (pintype "bidirectional"))
      (node (ref "U6") (pin "149") (pinfunction "CAM1_CN_149") (pintype "bidirectional"))
    )
    (net (code "13") (name "/C1_C_P") (class "Default")
      (node (ref "J14") (pin "9") (pinfunction "9_9") (pintype "bidirectional"))
      (node (ref "U6") (pin "147") (pinfunction "CAM1_CP_147") (pintype "bidirectional"))
    )
    (net (code "14") (name "/C1_D0_N") (class "Default")
      (node (ref "J14") (pin "2") (pinfunction "2_2") (pintype "bidirectional"))
      (node (ref "U6") (pin "161") (pinfunction "CAM1_DN0_161") (pintype "bidirectional"))
    )
    (net (code "15") (name "/C1_D0_P") (class "Default")
      (node (ref "J14") (pin "3") (pinfunction "3_3") (pintype "bidirectional"))
      (node (ref "U6") (pin "159") (pinfunction "CAM1_DP0_159") (pintype "bidirectional"))
    )
    (net (code "16") (name "/C1_D1_N") (class "Default")
      (node (ref "J14") (pin "5") (pinfunction "5_5") (pintype "bidirectional"))
      (node (ref "U6") (pin "155") (pinfunction "CAM1_DN1_155") (pintype "bidirectional"))
    )
    (net (code "17") (name "/C1_D1_P") (class "Default")
      (node (ref "J14") (pin "6") (pinfunction "6_6") (pintype "bidirectional"))
      (node (ref "U6") (pin "153") (pinfunction "CAM1_DP1_153") (pintype "bidirectional"))
    )
    (net (code "18") (name "/C1_IO0") (class "Default")
      (node (ref "J14") (pin "11") (pinfunction "11_11") (pintype "bidirectional"))
      (node (ref "U6") (pin "78") (pinfunction "GPIO43_78") (pintype "bidirectional"))
    )
    (net (code "19") (name "/C1_IO1") (class "Default")
      (node (ref "J14") (pin "12") (pinfunction "12_12") (pintype "bidirectional"))
      (node (ref "U6") (pin "76") (pinfunction "GPIO42_76") (pintype "bidirectional"))
    )
    (net (code "20") (name "/EMMC_DISABLE_N") (class "Default")
      (node (ref "U6") (pin "2") (pinfunction "EMMC_DISABLE_N_2") (pintype "bidirectional"))
    )
    (net (code "21") (name "/ETH_BIAS") (class "Default")
      (node (ref "C1") (pin "2") (pinfunction "2_2") (pintype "passive"))
      (node (ref "L4") (pin "2") (pinfunction "2_2") (pintype "passive"))
      (node (ref "U7") (pin "13") (pinfunction "ETH_BIAS_13") (pintype "bidirectional"))
    )
    (net (code "22") (name "/GEAR") (class "Default")
      (node (ref "JP1") (pin "1") (pinfunction "1_1") (pintype "passive"))
      (node (ref "U6") (pin "65") (pinfunction "GPIO19_65") (pintype "bidirectional"))
    )
    (net (code "23") (name "/GPCLK1") (class "Default")
      (node (ref "R10") (pin "1") (pinfunction "11_1") (pintype "passive"))
      (node (ref "U2") (pin "61") (pinfunction "XI_61") (pintype "input"))
      (node (ref "U6") (pin "82") (pinfunction "GPIO44_82") (pintype "bidirectional"))
    )
    (net (code "24") (name "/GPIO12") (class "Default")
      (node (ref "U6") (pin "45") (pinfunction "GPIO12_45") (pintype "bidirectional"))
    )
    (net (code "25") (name "/GPIO13") (class "Default")
      (node (ref "U6") (pin "47") (pinfunction "GPIO13_47") (pintype "bidirectional"))
    )
    (net (code "26") (name "/GPIO16") (class "Default")
      (node (ref "U6") (pin "57") (pinfunction "GPIO16_57") (pintype "bidirectional"))
    )
    (net (code "27") (name "/GPIO17") (class "Default")
      (node (ref "U6") (pin "59") (pinfunction "GPIO17_59") (pintype "bidirectional"))
    )
    (net (code "28") (name "/GPIO37") (class "Default")
      (node (ref "U6") (pin "60") (pinfunction "GPIO37_60") (pintype "bidirectional"))
    )
    (net (code "29") (name "/GPIO38") (class "Default")
      (node (ref "U6") (pin "64") (pinfunction "GPIO38_64") (pintype "bidirectional"))
    )
    (net (code "30") (name "/GPIO39") (class "Default")
      (node (ref "U6") (pin "66") (pinfunction "GPIO39_66") (pintype "bidirectional"))
    )
    (net (code "31") (name "/I2C_MPU_SCL") (class "Default")
      (node (ref "U10") (pin "61") (pinfunction "PB8_61") (pintype "bidirectional"))
      (node (ref "U9") (pin "3") (pinfunction "A1_3") (pintype "bidirectional"))
    )
    (net (code "32") (name "/I2C_MPU_SDA") (class "Default")
      (node (ref "U10") (pin "62") (pinfunction "PB9_62") (pintype "bidirectional"))
      (node (ref "U9") (pin "2") (pinfunction "A0_2") (pintype "bidirectional"))
    )
    (net (code "33") (name "/I2C_SCL") (class "Default")
      (node (ref "J1") (pin "3") (pinfunction "3_3") (pintype "bidirectional"))
      (node (ref "J10") (pin "3") (pinfunction "3_3") (pintype "bidirectional"))
      (node (ref "J11") (pin "3") (pinfunction "3_3") (pintype "bidirectional"))
      (node (ref "J15") (pin "3") (pinfunction "3_3") (pintype "bidirectional"))
      (node (ref "J16") (pin "3") (pinfunction "3_3") (pintype "bidirectional"))
      (node (ref "J17") (pin "3") (pinfunction "3_3") (pintype "bidirectional"))
      (node (ref "J18") (pin "3") (pinfunction "3_3") (pintype "bidirectional"))
      (node (ref "J19") (pin "3") (pinfunction "3_3") (pintype "bidirectional"))
      (node (ref "J2") (pin "3") (pinfunction "3_3") (pintype "bidirectional"))
      (node (ref "J20") (pin "3") (pinfunction "3_3") (pintype "bidirectional"))
      (node (ref "J21") (pin "3") (pinfunction "3_3") (pintype "bidirectional"))
      (node (ref "J22") (pin "3") (pinfunction "3_3") (pintype "bidirectional"))
      (node (ref "J7") (pin "20") (pinfunction "2020_20") (pintype "passive"))
      (node (ref "J9") (pin "3") (pinfunction "3_3") (pintype "bidirectional"))
      (node (ref "U3") (pin "8") (pinfunction "SCL_8") (pintype "bidirectional"))
      (node (ref "U4") (pin "19") (pinfunction "19_SCL/SPI_CLK_19") (pintype "bidirectional"))
      (node (ref "U6") (pin "11") (pinfunction "GPIO3_11") (pintype "bidirectional"))
    )
    (net (code "34") (name "/I2C_SCL_1V8") (class "Default")
      (node (ref "U1") (pin "23") (pinfunction "SCL/SCLK_23") (pintype "bidirectional"))
      (node (ref "U9") (pin "6") (pinfunction "B1_6") (pintype "bidirectional"))
    )
    (net (code "35") (name "/I2C_SDA") (class "Default")
      (node (ref "J1") (pin "2") (pinfunction "2_2") (pintype "bidirectional"))
      (node (ref "J10") (pin "2") (pinfunction "2_2") (pintype "bidirectional"))
      (node (ref "J11") (pin "2") (pinfunction "2_2") (pintype "bidirectional"))
      (node (ref "J15") (pin "2") (pinfunction "2_2") (pintype "bidirectional"))
      (node (ref "J16") (pin "2") (pinfunction "2_2") (pintype "bidirectional"))
      (node (ref "J17") (pin "2") (pinfunction "2_2") (pintype "bidirectional"))
      (node (ref "J18") (pin "2") (pinfunction "2_2") (pintype "bidirectional"))
      (node (ref "J19") (pin "2") (pinfunction "2_2") (pintype "bidirectional"))
      (node (ref "J2") (pin "2") (pinfunction "2_2") (pintype "bidirectional"))
      (node (ref "J20") (pin "2") (pinfunction "2_2") (pintype "bidirectional"))
      (node (ref "J21") (pin "2") (pinfunction "2_2") (pintype "bidirectional"))
      (node (ref "J22") (pin "2") (pinfunction "2_2") (pintype "bidirectional"))
      (node (ref "J7") (pin "19") (pinfunction "1919_19") (pintype "passive"))
      (node (ref "J9") (pin "2") (pinfunction "2_2") (pintype "bidirectional"))
      (node (ref "U3") (pin "7") (pinfunction "SDL_7") (pintype "bidirectional"))
      (node (ref "U4") (pin "18") (pinfunction "18_SDA/SPI_CS_N_18") (pintype "bidirectional"))
      (node (ref "U6") (pin "9") (pinfunction "GPIO2_9") (pintype "bidirectional"))
    )
    (net (code "36") (name "/I2C_SDA_1V8") (class "Default")
      (node (ref "U1") (pin "24") (pinfunction "SDA/SDI_24") (pintype "bidirectional"))
      (node (ref "U9") (pin "7") (pinfunction "B0_7") (pintype "bidirectional"))
    )
    (net (code "37") (name "/ID_SD") (class "Default")
      (node (ref "U11") (pin "CH_PD") (pinfunction "CH_PD_CH_PD") (pintype "bidirectional"))
      (node (ref "U6") (pin "15") (pinfunction "GPIO4_15") (pintype "bidirectional"))
    )
    (net (code "38") (name "/MISO") (class "Default")
      (node (ref "J7") (pin "13") (pinfunction "1313_13") (pintype "passive"))
      (node (ref "U6") (pin "52") (pinfunction "GPIO34_52") (pintype "bidirectional"))
    )
    (net (code "39") (name "/MOSI") (class "Default")
      (node (ref "J7") (pin "12") (pinfunction "1212_12") (pintype "passive"))
      (node (ref "U6") (pin "48") (pinfunction "GPIO33_48") (pintype "bidirectional"))
    )
    (net (code "40") (name "/NRST") (class "Default")
      (node (ref "U6") (pin "63") (pinfunction "GPIO18_63") (pintype "bidirectional"))
      (node (ref "U8") (pin "4") (pinfunction "3Z_4") (pintype "bidirectional"))
    )
    (net (code "41") (name "/NRST1") (class "Default")
      (node (ref "U10") (pin "7") (pinfunction "NRST_7") (pintype "bidirectional"))
      (node (ref "U8") (pin "5") (pinfunction "3Y0_5") (pintype "bidirectional"))
    )
    (net (code "42") (name "/NRST2") (class "Default")
      (node (ref "J7") (pin "17") (pinfunction "1717_17") (pintype "passive"))
      (node (ref "U8") (pin "3") (pinfunction "3Y1_3") (pintype "bidirectional"))
    )
    (net (code "43") (name "/PWM") (class "Default")
      (node (ref "J7") (pin "23") (pinfunction "2323_23") (pintype "passive"))
      (node (ref "U10") (pin "24") (pinfunction "PC4_24") (pintype "bidirectional"))
    )
    (net (code "44") (name "/PWM2") (class "Default")
      (node (ref "J7") (pin "24") (pinfunction "2424_24") (pintype "passive"))
      (node (ref "U10") (pin "25") (pinfunction "PC5_25") (pintype "bidirectional"))
    )
    (net (code "45") (name "/PWM3") (class "Default")
      (node (ref "J7") (pin "25") (pinfunction "2525_25") (pintype "passive"))
      (node (ref "U10") (pin "26") (pinfunction "PB0_26") (pintype "bidirectional"))
    )
    (net (code "46") (name "/PWM4") (class "Default")
      (node (ref "J7") (pin "26") (pinfunction "2626_26") (pintype "passive"))
      (node (ref "U10") (pin "27") (pinfunction "PB1_27") (pintype "bidirectional"))
    )
    (net (code "47") (name "/PWR_EN") (class "Default")
      (node (ref "J7") (pin "18") (pinfunction "1818_18") (pintype "passive"))
      (node (ref "U6") (pin "58") (pinfunction "GPIO36_58") (pintype "bidirectional"))
    )
    (net (code "48") (name "/RST") (class "Default")
      (node (ref "J7") (pin "11") (pinfunction "1111_11") (pintype "passive"))
      (node (ref "U6") (pin "46") (pinfunction "GPIO32_46") (pintype "bidirectional"))
    )
    (net (code "49") (name "/RX_LAN_N") (class "Default")
      (node (ref "R26") (pin "2") (pinfunction "22_2") (pintype "passive"))
      (node (ref "T1") (pin "1") (pinfunction "1_1") (pintype "bidirectional"))
      (node (ref "U7") (pin "57") (pinfunction "RX_N_LAN_57") (pintype "bidirectional"))
    )
    (net (code "50") (name "/RX_LAN_P") (class "Default")
      (node (ref "R25") (pin "2") (pinfunction "22_2") (pintype "passive"))
      (node (ref "T1") (pin "2") (pinfunction "2_2") (pintype "bidirectional"))
      (node (ref "U7") (pin "58") (pinfunction "RX_P_LAN_58") (pintype "bidirectional"))
    )
    (net (code "51") (name "/RX_N") (class "Default")
      (node (ref "R23") (pin "2") (pinfunction "22_2") (pintype "passive"))
      (node (ref "T1") (pin "5") (pinfunction "5_5") (pintype "bidirectional"))
      (node (ref "U2") (pin "53") (pinfunction "RXN_53") (pintype "bidirectional"))
    )
    (net (code "52") (name "/RX_P") (class "Default")
      (node (ref "R22") (pin "2") (pinfunction "22_2") (pintype "passive"))
      (node (ref "T1") (pin "4") (pinfunction "4_4") (pintype "bidirectional"))
      (node (ref "U2") (pin "52") (pinfunction "RXP_52") (pintype "bidirectional"))
    )
    (net (code "53") (name "/SCK") (class "Default")
      (node (ref "J7") (pin "14") (pinfunction "1414_14") (pintype "passive"))
      (node (ref "U6") (pin "54") (pinfunction "GPIO35_54") (pintype "bidirectional"))
    )
    (net (code "54") (name "/SCL0") (class "Default")
      (node (ref "J13") (pin "13") (pinfunction "13_13") (pintype "bidirectional"))
      (node (ref "R16") (pin "2") (pinfunction "22_2") (pintype "passive"))
      (node (ref "U6") (pin "30") (pinfunction "GPIO29_30") (pintype "bidirectional"))
    )
    (net (code "55") (name "/SCL1") (class "Default")
      (node (ref "J14") (pin "13") (pinfunction "13_13") (pintype "bidirectional"))
      (node (ref "R18") (pin "2") (pinfunction "22_2") (pintype "passive"))
      (node (ref "U6") (pin "5") (pinfunction "GPIO1_5") (pintype "bidirectional"))
    )
    (net (code "56") (name "/SDA0") (class "Default")
      (node (ref "J13") (pin "14") (pinfunction "14_14") (pintype "bidirectional"))
      (node (ref "R15") (pin "2") (pinfunction "22_2") (pintype "passive"))
      (node (ref "U6") (pin "28") (pinfunction "GPIO28_28") (pintype "bidirectional"))
    )
    (net (code "57") (name "/SDA1") (class "Default")
      (node (ref "J14") (pin "14") (pinfunction "14_14") (pintype "bidirectional"))
      (node (ref "R17") (pin "2") (pinfunction "22_2") (pintype "passive"))
      (node (ref "U6") (pin "3") (pinfunction "GPIO0_3") (pintype "bidirectional"))
    )
    (net (code "58") (name "/SDX_CLK") (class "Default")
      (node (ref "J8") (pin "5") (pinfunction "CLK_5") (pintype "bidirectional"))
      (node (ref "U6") (pin "10") (pinfunction "SDX_CLK_10") (pintype "bidirectional"))
    )
    (net (code "59") (name "/SDX_CMD") (class "Default")
      (node (ref "J8") (pin "3") (pinfunction "CMD_3") (pintype "bidirectional"))
      (node (ref "U6") (pin "12") (pinfunction "SDX_CMD_12") (pintype "bidirectional"))
    )
    (net (code "60") (name "/SDX_D0") (class "Default")
      (node (ref "J8") (pin "7") (pinfunction "DAT0_7") (pintype "bidirectional"))
      (node (ref "U6") (pin "16") (pinfunction "SDX_D0_16") (pintype "bidirectional"))
    )
    (net (code "61") (name "/SDX_D1") (class "Default")
      (node (ref "J8") (pin "8") (pinfunction "DAT1_8") (pintype "bidirectional"))
      (node (ref "U6") (pin "18") (pinfunction "SDX_D1_18") (pintype "bidirectional"))
    )
    (net (code "62") (name "/SDX_D2") (class "Default")
      (node (ref "J8") (pin "1") (pinfunction "DAT2_1") (pintype "bidirectional"))
      (node (ref "U6") (pin "22") (pinfunction "SDX_D2_22") (pintype "bidirectional"))
    )
    (net (code "63") (name "/SDX_D3") (class "Default")
      (node (ref "J8") (pin "2") (pinfunction "CD/DAT3_2") (pintype "bidirectional"))
      (node (ref "U6") (pin "24") (pinfunction "SDX_D3_24") (pintype "bidirectional"))
    )
    (net (code "64") (name "/SD_CLK") (class "Default")
      (node (ref "R9") (pin "2") (pinfunction "22_2") (pintype "passive"))
      (node (ref "U6") (pin "75") (pinfunction "GPIO22_75") (pintype "bidirectional"))
    )
    (net (code "65") (name "/SD_CMD") (class "Default")
      (node (ref "R3") (pin "2") (pinfunction "22_2") (pintype "passive"))
      (node (ref "U6") (pin "77") (pinfunction "GPIO23_77") (pintype "bidirectional"))
    )
    (net (code "66") (name "/SD_D0") (class "Default")
      (node (ref "R5") (pin "2") (pinfunction "22_2") (pintype "passive"))
      (node (ref "U6") (pin "81") (pinfunction "GPIO24_81") (pintype "bidirectional"))
    )
    (net (code "67") (name "/SD_D1") (class "Default")
      (node (ref "R8") (pin "2") (pinfunction "22_2") (pintype "passive"))
      (node (ref "U6") (pin "83") (pinfunction "GPIO25_83") (pintype "bidirectional"))
    )
    (net (code "68") (name "/SD_D2") (class "Default")
      (node (ref "R6") (pin "2") (pinfunction "22_2") (pintype "passive"))
      (node (ref "U6") (pin "87") (pinfunction "GPIO26_87") (pintype "bidirectional"))
    )
    (net (code "69") (name "/SD_D3") (class "Default")
      (node (ref "R7") (pin "2") (pinfunction "22_2") (pintype "passive"))
      (node (ref "U6") (pin "89") (pinfunction "GPIO27_89") (pintype "bidirectional"))
    )
    (net (code "70") (name "/SEL0") (class "Default")
      (node (ref "J7") (pin "9") (pinfunction "99_9") (pintype "passive"))
      (node (ref "U6") (pin "21") (pinfunction "GPIO6_21") (pintype "bidirectional"))
    )
    (net (code "71") (name "/SEL1") (class "Default")
      (node (ref "J7") (pin "10") (pinfunction "1010_10") (pintype "passive"))
      (node (ref "U6") (pin "23") (pinfunction "GPIO7_23") (pintype "bidirectional"))
    )
    (net (code "72") (name "/SEL2") (class "Default")
      (node (ref "U6") (pin "17") (pinfunction "GPIO5_17") (pintype "bidirectional"))
      (node (ref "U8") (pin "10") (pinfunction "S2_10") (pintype "bidirectional"))
      (node (ref "U8") (pin "11") (pinfunction "S1_11") (pintype "bidirectional"))
      (node (ref "U8") (pin "9") (pinfunction "S3_9") (pintype "bidirectional"))
    )
    (net (code "73") (name "/SPI_CS0") (class "Default")
      (node (ref "U10") (pin "20") (pinfunction "PA4_20") (pintype "bidirectional"))
      (node (ref "U6") (pin "27") (pinfunction "GPIO8_27") (pintype "bidirectional"))
    )
    (net (code "74") (name "/SPI_MISO") (class "Default")
      (node (ref "U10") (pin "22") (pinfunction "PA6_22") (pintype "bidirectional"))
      (node (ref "U6") (pin "29") (pinfunction "GPIO9_29") (pintype "bidirectional"))
    )
    (net (code "75") (name "/SPI_MOSI") (class "Default")
      (node (ref "U10") (pin "23") (pinfunction "PA7_23") (pintype "bidirectional"))
      (node (ref "U6") (pin "33") (pinfunction "GPIO10_33") (pintype "bidirectional"))
    )
    (net (code "76") (name "/SPI_SCLK") (class "Default")
      (node (ref "U10") (pin "21") (pinfunction "PA5_21") (pintype "bidirectional"))
      (node (ref "U6") (pin "35") (pinfunction "GPIO11_35") (pintype "bidirectional"))
    )
    (net (code "77") (name "/SWCLK") (class "Default")
      (node (ref "U6") (pin "69") (pinfunction "GPIO20_69") (pintype "bidirectional"))
      (node (ref "U8") (pin "15") (pinfunction "2Z_15") (pintype "bidirectional"))
    )
    (net (code "78") (name "/SWCLK1") (class "Default")
      (node (ref "U10") (pin "49") (pinfunction "PA14_49") (pintype "bidirectional"))
      (node (ref "U8") (pin "2") (pinfunction "2Y0_2") (pintype "bidirectional"))
    )
    (net (code "79") (name "/SWCLK2") (class "Default")
      (node (ref "J7") (pin "16") (pinfunction "1616_16") (pintype "passive"))
      (node (ref "U8") (pin "1") (pinfunction "2Y1_1") (pintype "bidirectional"))
    )
    (net (code "80") (name "/SWDIO") (class "Default")
      (node (ref "U6") (pin "71") (pinfunction "GPIO21_71") (pintype "bidirectional"))
      (node (ref "U8") (pin "14") (pinfunction "1Z_14") (pintype "bidirectional"))
    )
    (net (code "81") (name "/SWDIO1") (class "Default")
      (node (ref "U10") (pin "46") (pinfunction "PA13_46") (pintype "bidirectional"))
      (node (ref "U8") (pin "12") (pinfunction "1Y0_12") (pintype "bidirectional"))
    )
    (net (code "82") (name "/SWDIO2") (class "Default")
      (node (ref "J7") (pin "15") (pinfunction "1515_15") (pintype "passive"))
      (node (ref "U8") (pin "13") (pinfunction "1Y1_13") (pintype "bidirectional"))
    )
    (net (code "83") (name "/TX_LAN_N") (class "Default")
      (node (ref "R27") (pin "2") (pinfunction "22_2") (pintype "passive"))
      (node (ref "T2") (pin "2") (pinfunction "2_2") (pintype "bidirectional"))
      (node (ref "U7") (pin "56") (pinfunction "TX_N_LAN_56") (pintype "bidirectional"))
    )
    (net (code "84") (name "/TX_LAN_P") (class "Default")
      (node (ref "R24") (pin "2") (pinfunction "22_2") (pintype "passive"))
      (node (ref "T2") (pin "1") (pinfunction "1_1") (pintype "bidirectional"))
      (node (ref "U7") (pin "55") (pinfunction "TX_P_LAN_55") (pintype "bidirectional"))
    )
    (net (code "85") (name "/TX_N") (class "Default")
      (node (ref "R20") (pin "2") (pinfunction "22_2") (pintype "passive"))
      (node (ref "T2") (pin "4") (pinfunction "4_4") (pintype "bidirectional"))
      (node (ref "U2") (pin "56") (pinfunction "TXN_56") (pintype "bidirectional"))
    )
    (net (code "86") (name "/TX_P") (class "Default")
      (node (ref "R21") (pin "2") (pinfunction "22_2") (pintype "passive"))
      (node (ref "T2") (pin "5") (pinfunction "5_5") (pintype "bidirectional"))
      (node (ref "U2") (pin "55") (pinfunction "TXP_55") (pintype "bidirectional"))
    )
    (net (code "87") (name "/UART2_RX") (class "Default")
      (node (ref "J7") (pin "21") (pinfunction "2121_21") (pintype "passive"))
      (node (ref "U6") (pin "72") (pinfunction "GPIO41_72") (pintype "bidirectional"))
    )
    (net (code "88") (name "/UART2_TX") (class "Default")
      (node (ref "J7") (pin "22") (pinfunction "2222_22") (pintype "passive"))
      (node (ref "U6") (pin "70") (pinfunction "GPIO40_70") (pintype "bidirectional"))
    )
    (net (code "89") (name "/USART1_RX") (class "Default")
      (node (ref "J3") (pin "1") (pinfunction "1_1") (pintype "bidirectional"))
      (node (ref "U10") (pin "59") (pinfunction "PB7_59") (pintype "bidirectional"))
      (node (ref "U6") (pin "53") (pinfunction "GPIO15_53") (pintype "bidirectional"))
    )
    (net (code "90") (name "/USART1_TX") (class "Default")
      (node (ref "J3") (pin "2") (pinfunction "2_2") (pintype "bidirectional"))
      (node (ref "U6") (pin "51") (pinfunction "GPIO14_51") (pintype "bidirectional"))
    )
    (net (code "91") (name "/USB_D2_N") (class "Default")
      (node (ref "J12") (pin "2") (pinfunction "D-_2") (pintype "bidirectional"))
      (node (ref "U2") (pin "1") (pinfunction "USBDM2_1") (pintype "bidirectional"))
    )
    (net (code "92") (name "/USB_D2_P") (class "Default")
      (node (ref "J12") (pin "3") (pinfunction "D+_3") (pintype "bidirectional"))
      (node (ref "U2") (pin "2") (pinfunction "USBDP2_2") (pintype "bidirectional"))
    )
    (net (code "93") (name "/USB_D3_N") (class "Default")
      (node (ref "J4") (pin "2") (pinfunction "D-_2") (pintype "bidirectional"))
      (node (ref "U2") (pin "3") (pinfunction "USBDM3_3") (pintype "bidirectional"))
    )
    (net (code "94") (name "/USB_D3_P") (class "Default")
      (node (ref "J4") (pin "3") (pinfunction "D+_3") (pintype "bidirectional"))
      (node (ref "U2") (pin "4") (pinfunction "USBDP3_4") (pintype "bidirectional"))
    )
    (net (code "95") (name "/USB_D_N") (class "Default")
      (node (ref "U2") (pin "58") (pinfunction "USBDM0_58") (pintype "bidirectional"))
      (node (ref "U6") (pin "167") (pinfunction "USB_DM_167") (pintype "bidirectional"))
    )
    (net (code "96") (name "/USB_D_P") (class "Default")
      (node (ref "U2") (pin "59") (pinfunction "USBDP0_59") (pintype "bidirectional"))
      (node (ref "U6") (pin "165") (pinfunction "USB_DP_165") (pintype "bidirectional"))
    )
    (net (code "97") (name "1.8V") (class "Default")
      (node (ref "C11") (pin "2") (pinfunction "2_2") (pintype "passive"))
      (node (ref "C2") (pin "1") (pinfunction "1_1") (pintype "passive"))
      (node (ref "C66") (pin "2") (pinfunction "2_2") (pintype "passive"))
      (node (ref "C67") (pin "2") (pinfunction "22_2") (pintype "passive"))
      (node (ref "C9") (pin "1") (pinfunction "1_1") (pintype "passive"))
      (node (ref "U1") (pin "13") (pinfunction "VDD_13") (pintype "bidirectional"))
      (node (ref "U1") (pin "22") (pinfunction "CS_22") (pintype "bidirectional"))
      (node (ref "U1") (pin "8") (pinfunction "VDDIO_8") (pintype "bidirectional"))
      (node (ref "U1") (pin "9") (pinfunction "AD0/SDO_9") (pintype "bidirectional"))
      (node (ref "U5") (pin "2") (pinfunction "OUT_2") (pintype "bidirectional"))
      (node (ref "U5") (pin "4") (pinfunction "OUT_4") (pintype "bidirectional"))
      (node (ref "U6") (pin "183") (pinfunction "1V8_183") (pintype "bidirectional"))
      (node (ref "U6") (pin "184") (pinfunction "1V8_184") (pintype "bidirectional"))
      (node (ref "U6") (pin "185") (pinfunction "1V8_185") (pintype "bidirectional"))
      (node (ref "U6") (pin "186") (pinfunction "1V8_186") (pintype "bidirectional"))
      (node (ref "U9") (pin "8") (pinfunction "VCCB_8") (pintype "bidirectional"))
    )
    (net (code "98") (name "GND") (class "Default")
      (node (ref "C1") (pin "1") (pinfunction "1_1") (pintype "passive"))
      (node (ref "C10") (pin "1") (pinfunction "11_1") (pintype "passive"))
      (node (ref "C11") (pin "1") (pinfunction "1_1") (pintype "passive"))
      (node (ref "C12") (pin "1") (pinfunction "1_1") (pintype "passive"))
      (node (ref "C13") (pin "1") (pinfunction "1_1") (pintype "passive"))
      (node (ref "C14") (pin "1") (pinfunction "1_1") (pintype "passive"))
      (node (ref "C15") (pin "1") (pinfunction "1_1") (pintype "passive"))
      (node (ref "C16") (pin "1") (pinfunction "1_1") (pintype "passive"))
      (node (ref "C17") (pin "1") (pinfunction "1_1") (pintype "passive"))
      (node (ref "C18") (pin "1") (pinfunction "1_1") (pintype "passive"))
      (node (ref "C2") (pin "2") (pinfunction "2_2") (pintype "passive"))
      (node (ref "C20") (pin "1") (pinfunction "1_1") (pintype "passive"))
      (node (ref "C21") (pin "1") (pinfunction "11_1") (pintype "passive"))
      (node (ref "C24") (pin "1") (pinfunction "11_1") (pintype "passive"))
      (node (ref "C25") (pin "1") (pinfunction "1_1") (pintype "passive"))
      (node (ref "C26") (pin "1") (pinfunction "1_1") (pintype "passive"))
      (node (ref "C27") (pin "1") (pinfunction "1_1") (pintype "passive"))
      (node (ref "C28") (pin "1") (pinfunction "1_1") (pintype "passive"))
      (node (ref "C29") (pin "1") (pinfunction "1_1") (pintype "passive"))
      (node (ref "C3") (pin "1") (pinfunction "1_1") (pintype "passive"))
      (node (ref "C30") (pin "1") (pinfunction "1_1") (pintype "passive"))
      (node (ref "C31") (pin "1") (pinfunction "1_1") (pintype "passive"))
      (node (ref "C32") (pin "1") (pinfunction "1_1") (pintype "passive"))
      (node (ref "C33") (pin "1") (pinfunction "1_1") (pintype "passive"))
      (node (ref "C34") (pin "1") (pinfunction "1_1") (pintype "passive"))
      (node (ref "C35") (pin "1") (pinfunction "1_1") (pintype "passive"))
      (node (ref "C39") (pin "1") (pinfunction "1_1") (pintype "passive"))
      (node (ref "C4") (pin "1") (pinfunction "1_1") (pintype "bidirectional"))
      (node (ref "C40") (pin "1") (pinfunction "1_1") (pintype "passive"))
      (node (ref "C41") (pin "2") (pinfunction "22_2") (pintype "passive"))
      (node (ref "C42") (pin "2") (pinfunction "22_2") (pintype "passive"))
      (node (ref "C43") (pin "1") (pinfunction "11_1") (pintype "passive"))
      (node (ref "C5") (pin "1") (pinfunction "1_1") (pintype "passive"))
      (node (ref "C6") (pin "1") (pinfunction "11_1") (pintype "passive"))
      (node (ref "C62") (pin "1") (pinfunction "11_1") (pintype "passive"))
      (node (ref "C65") (pin "1") (pinfunction "1_1") (pintype "passive"))
      (node (ref "C66") (pin "1") (pinfunction "1_1") (pintype "passive"))
      (node (ref "C67") (pin "1") (pinfunction "11_1") (pintype "passive"))
      (node (ref "C7") (pin "1") (pinfunction "1_1") (pintype "passive"))
      (node (ref "C8") (pin "1") (pinfunction "1_1") (pintype "passive"))
      (node (ref "C9") (pin "2") (pinfunction "2_2") (pintype "passive"))
      (node (ref "D1") (pin "C") (pinfunction "C_C") (pintype "passive"))
      (node (ref "J1") (pin "4") (pinfunction "4_4") (pintype "bidirectional"))
      (node (ref "J10") (pin "4") (pinfunction "4_4") (pintype "bidirectional"))
      (node (ref "J11") (pin "4") (pinfunction "4_4") (pintype "bidirectional"))
      (node (ref "J12") (pin "4") (pinfunction "GND_4") (pintype "bidirectional"))
      (node (ref "J12") (pin "P$5") (pinfunction "GND_P$5") (pintype "bidirectional"))
      (node (ref "J12") (pin "P$6") (pinfunction "GND_P$6") (pintype "bidirectional"))
      (node (ref "J13") (pin "1") (pinfunction "1_1") (pintype "bidirectional"))
      (node (ref "J13") (pin "10") (pinfunction "10_10") (pintype "bidirectional"))
      (node (ref "J13") (pin "4") (pinfunction "4_4") (pintype "bidirectional"))
      (node (ref "J13") (pin "7") (pinfunction "7_7") (pintype "bidirectional"))
      (node (ref "J14") (pin "1") (pinfunction "1_1") (pintype "bidirectional"))
      (node (ref "J14") (pin "10") (pinfunction "10_10") (pintype "bidirectional"))
      (node (ref "J14") (pin "4") (pinfunction "4_4") (pintype "bidirectional"))
      (node (ref "J14") (pin "7") (pinfunction "7_7") (pintype "bidirectional"))
      (node (ref "J15") (pin "4") (pinfunction "4_4") (pintype "bidirectional"))
      (node (ref "J16") (pin "4") (pinfunction "4_4") (pintype "bidirectional"))
      (node (ref "J17") (pin "4") (pinfunction "4_4") (pintype "bidirectional"))
      (node (ref "J18") (pin "4") (pinfunction "4_4") (pintype "bidirectional"))
      (node (ref "J19") (pin "4") (pinfunction "4_4") (pintype "bidirectional"))
      (node (ref "J2") (pin "4") (pinfunction "4_4") (pintype "bidirectional"))
      (node (ref "J20") (pin "4") (pinfunction "4_4") (pintype "bidirectional"))
      (node (ref "J21") (pin "4") (pinfunction "4_4") (pintype "bidirectional"))
      (node (ref "J22") (pin "4") (pinfunction "4_4") (pintype "bidirectional"))
      (node (ref "J3") (pin "4") (pinfunction "4_4") (pintype "bidirectional"))
      (node (ref "J4") (pin "4") (pinfunction "GND_4") (pintype "bidirectional"))
      (node (ref "J4") (pin "P$5") (pinfunction "GND_P$5") (pintype "bidirectional"))
      (node (ref "J4") (pin "P$6") (pinfunction "GND_P$6") (pintype "bidirectional"))
      (node (ref "J5") (pin "P$1") (pinfunction "GND_P$1") (pintype "bidirectional"))
      (node (ref "J5") (pin "P$2") (pinfunction "GND_P$2") (pintype "bidirectional"))
      (node (ref "J7") (pin "27") (pinfunction "2727_27") (pintype "passive"))
      (node (ref "J7") (pin "28") (pinfunction "2828_28") (pintype "passive"))
      (node (ref "J7") (pin "29") (pinfunction "2929_29") (pintype "passive"))
      (node (ref "J7") (pin "30") (pinfunction "3030_30") (pintype "passive"))
      (node (ref "J7") (pin "7") (pinfunction "77_7") (pintype "passive"))
      (node (ref "J7") (pin "8") (pinfunction "88_8") (pintype "passive"))
      (node (ref "J8") (pin "10") (pinfunction "VSS_10") (pintype "bidirectional"))
      (node (ref "J8") (pin "11") (pinfunction "VSS_11") (pintype "bidirectional"))
      (node (ref "J8") (pin "12") (pinfunction "VSS_12") (pintype "bidirectional"))
      (node (ref "J8") (pin "13") (pinfunction "VSS_13") (pintype "bidirectional"))
      (node (ref "J8") (pin "6") (pinfunction "VSS_6") (pintype "bidirectional"))
      (node (ref "J8") (pin "9") (pinfunction "VSS_9") (pintype "bidirectional"))
      (node (ref "J9") (pin "4") (pinfunction "4_4") (pintype "bidirectional"))
      (node (ref "R1") (pin "2") (pinfunction "22_2") (pintype "passive"))
      (node (ref "R10") (pin "2") (pinfunction "22_2") (pintype "passive"))
      (node (ref "R14") (pin "1") (pinfunction "11_1") (pintype "passive"))
      (node (ref "R31") (pin "2") (pinfunction "22_2") (pintype "passive"))
      (node (ref "R32") (pin "2") (pinfunction "22_2") (pintype "passive"))
      (node (ref "R4") (pin "1") (pinfunction "11_1") (pintype "passive"))
      (node (ref "U1") (pin "11") (pinfunction "FSYNC_11") (pintype "bidirectional"))
      (node (ref "U1") (pin "18") (pinfunction "GND_18") (pintype "bidirectional"))
      (node (ref "U1") (pin "20") (pinfunction "GND_20") (pintype "bidirectional"))
      (node (ref "U10") (pin "12") (pinfunction "VSSA_12") (pintype "bidirectional"))
      (node (ref "U10") (pin "18") (pinfunction "VSS_18") (pintype "bidirectional"))
      (node (ref "U10") (pin "31") (pinfunction "VSS_31") (pintype "bidirectional"))
      (node (ref "U10") (pin "47") (pinfunction "VSS_47") (pintype "bidirectional"))
      (node (ref "U10") (pin "63") (pinfunction "VSS_63") (pintype "bidirectional"))
      (node (ref "U11") (pin "GND") (pinfunction "GND_GND") (pintype "bidirectional"))
      (node (ref "U2") (pin "34") (pinfunction "TEST2_34") (pintype "passive"))
      (node (ref "U2") (pin "44") (pinfunction "CLK24_EN_44") (pintype "input"))
      (node (ref "U2") (pin "65") (pinfunction "EPAD_65") (pintype "passive"))
      (node (ref "U3") (pin "3") (pinfunction "GND_3") (pintype "bidirectional"))
      (node (ref "U4") (pin "10") (pinfunction "10_GND_10") (pintype "bidirectional"))
      (node (ref "U4") (pin "12") (pinfunction "12_GND_12") (pintype "bidirectional"))
      (node (ref "U4") (pin "13") (pinfunction "13_GND_13") (pintype "bidirectional"))
      (node (ref "U4") (pin "24") (pinfunction "24_GND_24") (pintype "bidirectional"))
      (node (ref "U4") (pin "7") (pinfunction "7_VDD_USB_7") (pintype "bidirectional"))
      (node (ref "U5") (pin "1") (pinfunction "GND_1") (pintype "bidirectional"))
      (node (ref "U6") (pin "1") (pinfunction "GND_1") (pintype "bidirectional"))
      (node (ref "U6") (pin "103") (pinfunction "GND_103") (pintype "bidirectional"))
      (node (ref "U6") (pin "104") (pinfunction "GND_104") (pintype "bidirectional"))
      (node (ref "U6") (pin "109") (pinfunction "GND_109") (pintype "bidirectional"))
      (node (ref "U6") (pin "110") (pinfunction "GND_110") (pintype "bidirectional"))
      (node (ref "U6") (pin "115") (pinfunction "GND_115") (pintype "bidirectional"))
      (node (ref "U6") (pin "116") (pinfunction "GND_116") (pintype "bidirectional"))
      (node (ref "U6") (pin "121") (pinfunction "GND_121") (pintype "bidirectional"))
      (node (ref "U6") (pin "122") (pinfunction "GND_122") (pintype "bidirectional"))
      (node (ref "U6") (pin "127") (pinfunction "GND_127") (pintype "bidirectional"))
      (node (ref "U6") (pin "13") (pinfunction "GND_13") (pintype "bidirectional"))
      (node (ref "U6") (pin "133") (pinfunction "GND_133") (pintype "bidirectional"))
      (node (ref "U6") (pin "134") (pinfunction "GND_134") (pintype "bidirectional"))
      (node (ref "U6") (pin "139") (pinfunction "GND_139") (pintype "bidirectional"))
      (node (ref "U6") (pin "14") (pinfunction "GND_14") (pintype "bidirectional"))
      (node (ref "U6") (pin "140") (pinfunction "GND_140") (pintype "bidirectional"))
      (node (ref "U6") (pin "145") (pinfunction "GND_145") (pintype "bidirectional"))
      (node (ref "U6") (pin "146") (pinfunction "GND_146") (pintype "bidirectional"))
      (node (ref "U6") (pin "151") (pinfunction "GND_151") (pintype "bidirectional"))
      (node (ref "U6") (pin "152") (pinfunction "GND_152") (pintype "bidirectional"))
      (node (ref "U6") (pin "157") (pinfunction "GND_157") (pintype "bidirectional"))
      (node (ref "U6") (pin "163") (pinfunction "GND_163") (pintype "bidirectional"))
      (node (ref "U6") (pin "164") (pinfunction "GND_164") (pintype "bidirectional"))
      (node (ref "U6") (pin "169") (pinfunction "GND_169") (pintype "bidirectional"))
      (node (ref "U6") (pin "170") (pinfunction "GND_170") (pintype "bidirectional"))
      (node (ref "U6") (pin "181") (pinfunction "GND_181") (pintype "bidirectional"))
      (node (ref "U6") (pin "182") (pinfunction "GND_182") (pintype "bidirectional"))
      (node (ref "U6") (pin "187") (pinfunction "GND_187") (pintype "bidirectional"))
      (node (ref "U6") (pin "188") (pinfunction "GND_188") (pintype "bidirectional"))
      (node (ref "U6") (pin "19") (pinfunction "GND_19") (pintype "bidirectional"))
      (node (ref "U6") (pin "195") (pinfunction "GND_195") (pintype "bidirectional"))
      (node (ref "U6") (pin "196") (pinfunction "GND_196") (pintype "bidirectional"))
      (node (ref "U6") (pin "20") (pinfunction "GND_20") (pintype "bidirectional"))
      (node (ref "U6") (pin "25") (pinfunction "GND_25") (pintype "bidirectional"))
      (node (ref "U6") (pin "26") (pinfunction "GND_26") (pintype "bidirectional"))
      (node (ref "U6") (pin "31") (pinfunction "GND_31") (pintype "bidirectional"))
      (node (ref "U6") (pin "32") (pinfunction "GND_32") (pintype "bidirectional"))
      (node (ref "U6") (pin "37") (pinfunction "GND_37") (pintype "bidirectional"))
      (node (ref "U6") (pin "38") (pinfunction "GND_38") (pintype "bidirectional"))
      (node (ref "U6") (pin "43") (pinfunction "GND_43") (pintype "bidirectional"))
      (node (ref "U6") (pin "44") (pinfunction "GND_44") (pintype "bidirectional"))
      (node (ref "U6") (pin "49") (pinfunction "GND_49") (pintype "bidirectional"))
      (node (ref "U6") (pin "50") (pinfunction "GND_50") (pintype "bidirectional"))
      (node (ref "U6") (pin "55") (pinfunction "GND_55") (pintype "bidirectional"))
      (node (ref "U6") (pin "56") (pinfunction "GND_56") (pintype "bidirectional"))
      (node (ref "U6") (pin "61") (pinfunction "GND_61") (pintype "bidirectional"))
      (node (ref "U6") (pin "62") (pinfunction "GND_62") (pintype "bidirectional"))
      (node (ref "U6") (pin "67") (pinfunction "GND_67") (pintype "bidirectional"))
      (node (ref "U6") (pin "68") (pinfunction "GND_68") (pintype "bidirectional"))
      (node (ref "U6") (pin "7") (pinfunction "GND_7") (pintype "bidirectional"))
      (node (ref "U6") (pin "73") (pinfunction "GND_73") (pintype "bidirectional"))
      (node (ref "U6") (pin "74") (pinfunction "GND_74") (pintype "bidirectional"))
      (node (ref "U6") (pin "79") (pinfunction "GND_79") (pintype "bidirectional"))
      (node (ref "U6") (pin "8") (pinfunction "GND_8") (pintype "bidirectional"))
      (node (ref "U6") (pin "80") (pinfunction "GND_80") (pintype "bidirectional"))
      (node (ref "U6") (pin "85") (pinfunction "GND_85") (pintype "bidirectional"))
      (node (ref "U6") (pin "86") (pinfunction "GND_86") (pintype "bidirectional"))
      (node (ref "U6") (pin "91") (pinfunction "GND_91") (pintype "bidirectional"))
      (node (ref "U6") (pin "92") (pinfunction "GND_92") (pintype "bidirectional"))
      (node (ref "U6") (pin "97") (pinfunction "GND_97") (pintype "bidirectional"))
      (node (ref "U6") (pin "98") (pinfunction "GND_98") (pintype "bidirectional"))
      (node (ref "U6") (pin "G1") (pinfunction "G1_G1") (pintype "bidirectional"))
      (node (ref "U6") (pin "G2") (pinfunction "G2_G2") (pintype "bidirectional"))
      (node (ref "U7") (pin "1") (pinfunction "GND_1") (pintype "bidirectional"))
      (node (ref "U7") (pin "17") (pinfunction "GND_17") (pintype "bidirectional"))
      (node (ref "U7") (pin "25") (pinfunction "GND_25") (pintype "bidirectional"))
      (node (ref "U7") (pin "26") (pinfunction "GND_26") (pintype "bidirectional"))
      (node (ref "U7") (pin "39") (pinfunction "GND_39") (pintype "bidirectional"))
      (node (ref "U7") (pin "40") (pinfunction "GND_40") (pintype "bidirectional"))
      (node (ref "U7") (pin "65") (pinfunction "65_65") (pintype "bidirectional"))
      (node (ref "U7") (pin "66") (pinfunction "66_66") (pintype "bidirectional"))
      (node (ref "U7") (pin "67") (pinfunction "67_67") (pintype "bidirectional"))
      (node (ref "U7") (pin "68") (pinfunction "68_68") (pintype "bidirectional"))
      (node (ref "U7") (pin "69") (pinfunction "69_69") (pintype "bidirectional"))
      (node (ref "U7") (pin "70") (pinfunction "70_70") (pintype "bidirectional"))
      (node (ref "U7") (pin "71") (pinfunction "71_71") (pintype "bidirectional"))
      (node (ref "U7") (pin "72") (pinfunction "72_72") (pintype "bidirectional"))
      (node (ref "U7") (pin "73") (pinfunction "73_73") (pintype "bidirectional"))
      (node (ref "U7") (pin "74") (pinfunction "74_74") (pintype "bidirectional"))
      (node (ref "U7") (pin "75") (pinfunction "75_75") (pintype "bidirectional"))
      (node (ref "U7") (pin "76") (pinfunction "76_76") (pintype "bidirectional"))
      (node (ref "U7") (pin "77") (pinfunction "77_77") (pintype "bidirectional"))
      (node (ref "U7") (pin "78") (pinfunction "78_78") (pintype "bidirectional"))
      (node (ref "U7") (pin "79") (pinfunction "79_79") (pintype "bidirectional"))
      (node (ref "U7") (pin "80") (pinfunction "80_80") (pintype "bidirectional"))
      (node (ref "U8") (pin "6") (pinfunction "~{E}_6") (pintype "bidirectional"))
      (node (ref "U8") (pin "7") (pinfunction "GND_7") (pintype "bidirectional"))
      (node (ref "U8") (pin "8") (pinfunction "GND_8") (pintype "bidirectional"))
      (node (ref "U9") (pin "4") (pinfunction "GND_4") (pintype "bidirectional"))
    )
    (net (code "99") (name "Net-(C6-22)") (class "Default")
      (node (ref "C6") (pin "2") (pinfunction "22_2") (pintype "passive"))
      (node (ref "L2") (pin "2") (pinfunction "2_2") (pintype "passive"))
      (node (ref "U2") (pin "62") (pinfunction "VDD18USBPLL_62") (pintype "power_in"))
    )
    (net (code "100") (name "Net-(J5-SIGNAL)") (class "Default")
      (node (ref "J5") (pin "P$3") (pinfunction "SIGNAL_P$3") (pintype "bidirectional"))
      (node (ref "L1") (pin "P$1") (pinfunction "1_P$1") (pintype "passive"))
      (node (ref "U4") (pin "11") (pinfunction "11_RF_IN_11") (pintype "bidirectional"))
    )
    (net (code "101") (name "Net-(L1-2)") (class "Default")
      (node (ref "C4") (pin "2") (pinfunction "2_2") (pintype "bidirectional"))
      (node (ref "L1") (pin "P$2") (pinfunction "2_P$2") (pintype "passive"))
      (node (ref "R12") (pin "2") (pinfunction "22_2") (pintype "passive"))
    )
    (net (code "102") (name "Net-(R1-11)") (class "Default")
      (node (ref "R1") (pin "1") (pinfunction "11_1") (pintype "passive"))
      (node (ref "U2") (pin "63") (pinfunction "USBRBIAS_63") (pintype "input"))
    )
    (net (code "103") (name "Net-(R2-22)") (class "Default")
      (node (ref "R2") (pin "2") (pinfunction "22_2") (pintype "passive"))
      (node (ref "U7") (pin "15") (pinfunction "CONFIG_15") (pintype "bidirectional"))
    )
    (net (code "104") (name "Net-(R3-11)") (class "Default")
      (node (ref "R3") (pin "1") (pinfunction "11_1") (pintype "passive"))
      (node (ref "U11") (pin "CS0") (pinfunction "CS0_CS0") (pintype "bidirectional"))
    )
    (net (code "105") (name "Net-(R4-22)") (class "Default")
      (node (ref "R4") (pin "2") (pinfunction "22_2") (pintype "passive"))
      (node (ref "U2") (pin "50") (pinfunction "EXRES_50") (pintype "input"))
    )
    (net (code "106") (name "Net-(R5-11)") (class "Default")
      (node (ref "R5") (pin "1") (pinfunction "11_1") (pintype "passive"))
      (node (ref "U11") (pin "MISO") (pinfunction "MISO_MISO") (pintype "bidirectional"))
    )
    (net (code "107") (name "Net-(R6-11)") (class "Default")
      (node (ref "R6") (pin "1") (pinfunction "11_1") (pintype "passive"))
      (node (ref "U11") (pin "GPIO9") (pinfunction "*GPIO9_GPIO9") (pintype "bidirectional"))
    )
    (net (code "108") (name "Net-(R7-11)") (class "Default")
      (node (ref "R7") (pin "1") (pinfunction "11_1") (pintype "passive"))
      (node (ref "U11") (pin "GPIO10") (pinfunction "*GPIO10_GPIO10") (pintype "bidirectional"))
    )
    (net (code "109") (name "Net-(R8-11)") (class "Default")
      (node (ref "R8") (pin "1") (pinfunction "11_1") (pintype "passive"))
      (node (ref "U11") (pin "MOSI") (pinfunction "MOSI_MOSI") (pintype "bidirectional"))
    )
    (net (code "110") (name "Net-(R9-11)") (class "Default")
      (node (ref "R9") (pin "1") (pinfunction "11_1") (pintype "passive"))
      (node (ref "U11") (pin "SCLK") (pinfunction "SCLK_SCLK") (pintype "bidirectional"))
    )
    (net (code "111") (name "Net-(R12-11)") (class "Default")
      (node (ref "R12") (pin "1") (pinfunction "11_1") (pintype "passive"))
      (node (ref "U4") (pin "9") (pinfunction "9_VCC_RF_9") (pintype "bidirectional"))
    )
    (net (code "112") (name "Net-(R14-22)") (class "Default")
      (node (ref "R14") (pin "2") (pinfunction "22_2") (pintype "passive"))
      (node (ref "U10") (pin "60") (pinfunction "BOOT0_60") (pintype "bidirectional"))
    )
    (net (code "113") (name "Net-(R19-11)") (class "Default")
      (node (ref "D1") (pin "A") (pinfunction "A_A") (pintype "passive"))
      (node (ref "R19") (pin "1") (pinfunction "11_1") (pintype "passive"))
    )
    (net (code "114") (name "Net-(R24-11)") (class "Default")
      (node (ref "C12") (pin "2") (pinfunction "2_2") (pintype "passive"))
      (node (ref "C3") (pin "2") (pinfunction "2_2") (pintype "passive"))
      (node (ref "L4") (pin "1") (pinfunction "1_1") (pintype "passive"))
      (node (ref "R24") (pin "1") (pinfunction "11_1") (pintype "passive"))
      (node (ref "R25") (pin "1") (pinfunction "11_1") (pintype "passive"))
      (node (ref "R26") (pin "1") (pinfunction "11_1") (pintype "passive"))
      (node (ref "R27") (pin "1") (pinfunction "11_1") (pintype "passive"))
      (node (ref "T1") (pin "6") (pinfunction "6_6") (pintype "bidirectional"))
      (node (ref "T2") (pin "6") (pinfunction "6_6") (pintype "bidirectional"))
    )
    (net (code "115") (name "Net-(R28-11)") (class "Default")
      (node (ref "D2") (pin "A") (pinfunction "A_A") (pintype "passive"))
      (node (ref "R28") (pin "1") (pinfunction "11_1") (pintype "passive"))
    )
    (net (code "116") (name "Net-(R29-11)") (class "Default")
      (node (ref "R29") (pin "1") (pinfunction "11_1") (pintype "passive"))
      (node (ref "U2") (pin "41") (pinfunction "AUTOMDIX_EN_41") (pintype "input"))
    )
    (net (code "117") (name "Net-(R31-11)") (class "Default")
      (node (ref "D4") (pin "C") (pinfunction "C_C") (pintype "passive"))
      (node (ref "R31") (pin "1") (pinfunction "11_1") (pintype "passive"))
    )
    (net (code "118") (name "Net-(R32-11)") (class "Default")
      (node (ref "R32") (pin "1") (pinfunction "11_1") (pintype "passive"))
      (node (ref "U6") (pin "168") (pinfunction "USB_OTGID_168") (pintype "bidirectional"))
    )
    (net (code "119") (name "Net-(U1-REGOUT)") (class "Default")
      (node (ref "C34") (pin "2") (pinfunction "2_2") (pintype "passive"))
      (node (ref "U1") (pin "10") (pinfunction "REGOUT_10") (pintype "bidirectional"))
    )
    (net (code "120") (name "Net-(U2B-VDD18CORE)") (class "Default")
      (node (ref "C18") (pin "2") (pinfunction "2_2") (pintype "passive"))
      (node (ref "C32") (pin "2") (pinfunction "2_2") (pintype "passive"))
      (node (ref "C33") (pin "2") (pinfunction "2_2") (pintype "passive"))
      (node (ref "U2") (pin "15") (pinfunction "VDD18CORE_2_15") (pintype "power_in"))
      (node (ref "U2") (pin "38") (pinfunction "VDD18CORE_38") (pintype "power_in"))
    )
    (net (code "121") (name "Net-(U2B-VDD18ETHPLL)") (class "Default")
      (node (ref "C31") (pin "2") (pinfunction "2_2") (pintype "passive"))
      (node (ref "L2") (pin "1") (pinfunction "1_1") (pintype "passive"))
      (node (ref "U2") (pin "48") (pinfunction "VDD18ETHPLL_48") (pintype "power_in"))
    )
    (net (code "122") (name "Net-(U3-CAP)") (class "Default")
      (node (ref "C40") (pin "2") (pinfunction "2_2") (pintype "passive"))
      (node (ref "U3") (pin "2") (pinfunction "CAP_2") (pintype "bidirectional"))
    )
    (net (code "123") (name "Net-(U7-CPU_STAT_LED)") (class "Default")
      (node (ref "D4") (pin "A") (pinfunction "A_A") (pintype "passive"))
      (node (ref "U7") (pin "11") (pinfunction "CPU_STAT_LED_11") (pintype "bidirectional"))
    )
    (net (code "124") (name "Net-(U7-LINK_LED_LAN)") (class "Default")
      (node (ref "D2") (pin "C") (pinfunction "C_C") (pintype "passive"))
      (node (ref "U7") (pin "60") (pinfunction "LINK_LED_LAN_60") (pintype "bidirectional"))
    )
    (net (code "125") (name "Net-(U10-VCAP_1)") (class "Default")
      (node (ref "C5") (pin "2") (pinfunction "2_2") (pintype "passive"))
      (node (ref "U10") (pin "30") (pinfunction "VCAP_1_30") (pintype "bidirectional"))
    )
    (net (code "126") (name "unconnected-(J7-3131-Pad31)") (class "Default")
      (node (ref "J7") (pin "31") (pinfunction "3131_31") (pintype "passive"))
    )
    (net (code "127") (name "unconnected-(J7-3232-Pad32)") (class "Default")
      (node (ref "J7") (pin "32") (pinfunction "3232_32") (pintype "passive"))
    )
    (net (code "128") (name "unconnected-(J7-3333-Pad33)") (class "Default")
      (node (ref "J7") (pin "33") (pinfunction "3333_33") (pintype "passive"))
    )
    (net (code "129") (name "unconnected-(J7-3434-Pad34)") (class "Default")
      (node (ref "J7") (pin "34") (pinfunction "3434_34") (pintype "passive"))
    )
    (net (code "130") (name "unconnected-(U1-AUX_CL-Pad7)") (class "Default")
      (node (ref "U1") (pin "7") (pinfunction "AUX_CL_7") (pintype "bidirectional"))
    )
    (net (code "131") (name "unconnected-(U1-AUX_DA-Pad21)") (class "Default")
      (node (ref "U1") (pin "21") (pinfunction "AUX_DA_21") (pintype "bidirectional"))
    )
    (net (code "132") (name "unconnected-(U1-INT1-Pad12)") (class "Default")
      (node (ref "U1") (pin "12") (pinfunction "INT1_12") (pintype "bidirectional"))
    )
    (net (code "133") (name "unconnected-(U2A-CLK24_OUT-Pad45)") (class "Default")
      (node (ref "U2") (pin "45") (pinfunction "CLK24_OUT_45") (pintype "output"))
    )
    (net (code "134") (name "unconnected-(U2A-EECLK-Pad23)") (class "Default")
      (node (ref "U2") (pin "23") (pinfunction "EECLK_23") (pintype "output"))
    )
    (net (code "135") (name "unconnected-(U2A-EECS-Pad24)") (class "Default")
      (node (ref "U2") (pin "24") (pinfunction "EECS_24") (pintype "output"))
    )
    (net (code "136") (name "unconnected-(U2A-EEDI-Pad26)") (class "Default")
      (node (ref "U2") (pin "26") (pinfunction "EEDI_26") (pintype "input"))
    )
    (net (code "137") (name "unconnected-(U2A-EEDO-Pad25)") (class "Default")
      (node (ref "U2") (pin "25") (pinfunction "EEDO_25") (pintype "output"))
    )
    (net (code "138") (name "unconnected-(U2A-GPIO3-Pad35)") (class "Default")
      (node (ref "U2") (pin "35") (pinfunction "GPIO3_35") (pintype "bidirectional"))
    )
    (net (code "139") (name "unconnected-(U2A-GPIO4-Pad36)") (class "Default")
      (node (ref "U2") (pin "36") (pinfunction "GPIO4_36") (pintype "bidirectional"))
    )
    (net (code "140") (name "unconnected-(U2A-GPIO5-Pad37)") (class "Default")
      (node (ref "U2") (pin "37") (pinfunction "GPIO5_37") (pintype "bidirectional"))
    )
    (net (code "141") (name "unconnected-(U2A-GPIO6-Pad42)") (class "Default")
      (node (ref "U2") (pin "42") (pinfunction "GPIO6_42") (pintype "bidirectional"))
    )
    (net (code "142") (name "unconnected-(U2A-GPIO7-Pad43)") (class "Default")
      (node (ref "U2") (pin "43") (pinfunction "GPIO7_43") (pintype "bidirectional"))
    )
    (net (code "143") (name "unconnected-(U2A-NFDX_LED{slash}GPIO0-Pad20)") (class "Default")
      (node (ref "U2") (pin "20") (pinfunction "NFDX_LED/GPIO0_20") (pintype "bidirectional"))
    )
    (net (code "144") (name "unconnected-(U2A-NLNKA_LED{slash}GPIO1-Pad21)") (class "Default")
      (node (ref "U2") (pin "21") (pinfunction "NLNKA_LED/GPIO1_21") (pintype "bidirectional"))
    )
    (net (code "145") (name "unconnected-(U2A-NSPD_LED{slash}GPIO2-Pad22)") (class "Default")
      (node (ref "U2") (pin "22") (pinfunction "NSPD_LED/GPIO2_22") (pintype "bidirectional"))
    )
    (net (code "146") (name "unconnected-(U2A-NTRST-Pad28)") (class "Default")
      (node (ref "U2") (pin "28") (pinfunction "NTRST_28") (pintype "input"))
    )
    (net (code "147") (name "unconnected-(U2A-PRTCTL3-Pad16)") (class "Default")
      (node (ref "U2") (pin "16") (pinfunction "PRTCTL3_16") (pintype "bidirectional"))
    )
    (net (code "148") (name "unconnected-(U2A-PRTXTL2-Pad14)") (class "Default")
      (node (ref "U2") (pin "14") (pinfunction "PRTXTL2_14") (pintype "bidirectional"))
    )
    (net (code "149") (name "unconnected-(U2A-TCK-Pad32)") (class "Default")
      (node (ref "U2") (pin "32") (pinfunction "TCK_32") (pintype "input"))
    )
    (net (code "150") (name "unconnected-(U2A-TDI-Pad30)") (class "Default")
      (node (ref "U2") (pin "30") (pinfunction "TDI_30") (pintype "input"))
    )
    (net (code "151") (name "unconnected-(U2A-TDO-Pad31)") (class "Default")
      (node (ref "U2") (pin "31") (pinfunction "TDO_31") (pintype "output"))
    )
    (net (code "152") (name "unconnected-(U2A-TEST1-Pad13)") (class "Default")
      (node (ref "U2") (pin "13") (pinfunction "TEST1_13") (pintype "passive"))
    )
    (net (code "153") (name "unconnected-(U2A-TEST4-Pad47)") (class "Default")
      (node (ref "U2") (pin "47") (pinfunction "TEST4_47") (pintype "passive"))
    )
    (net (code "154") (name "unconnected-(U2A-TMS-Pad29)") (class "Default")
      (node (ref "U2") (pin "29") (pinfunction "TMS_29") (pintype "input"))
    )
    (net (code "155") (name "unconnected-(U2A-XO-Pad60)") (class "Default")
      (node (ref "U2") (pin "60") (pinfunction "XO_60") (pintype "output"))
    )
    (net (code "156") (name "unconnected-(U2B-NC-Pad18)") (class "Default")
      (node (ref "U2") (pin "18") (pinfunction "NC_18") (pintype "no_connect"))
    )
    (net (code "157") (name "unconnected-(U2B-NC_2-Pad6)") (class "Default")
      (node (ref "U2") (pin "6") (pinfunction "NC_2_6") (pintype "no_connect"))
    )
    (net (code "158") (name "unconnected-(U2B-NC_3-Pad7)") (class "Default")
      (node (ref "U2") (pin "7") (pinfunction "NC_3_7") (pintype "no_connect"))
    )
    (net (code "159") (name "unconnected-(U2B-NC_4-Pad8)") (class "Default")
      (node (ref "U2") (pin "8") (pinfunction "NC_4_8") (pintype "no_connect"))
    )
    (net (code "160") (name "unconnected-(U2B-NC_5-Pad9)") (class "Default")
      (node (ref "U2") (pin "9") (pinfunction "NC_5_9") (pintype "no_connect"))
    )
    (net (code "161") (name "unconnected-(U2B-NC_6-Pad17)") (class "Default")
      (node (ref "U2") (pin "17") (pinfunction "NC_6_17") (pintype "no_connect"))
    )
    (net (code "162") (name "unconnected-(U3-INT1-Pad6)") (class "Default")
      (node (ref "U3") (pin "6") (pinfunction "INT1_6") (pintype "bidirectional"))
    )
    (net (code "163") (name "unconnected-(U3-INT2-Pad5)") (class "Default")
      (node (ref "U3") (pin "5") (pinfunction "INT2_5") (pintype "bidirectional"))
    )
    (net (code "164") (name "unconnected-(U4-1_SAFEBOOT_N-Pad1)") (class "Default")
      (node (ref "U4") (pin "1") (pinfunction "1_SAFEBOOT_N_1") (pintype "bidirectional"))
    )
    (net (code "165") (name "unconnected-(U4-2_D_SEL-Pad2)") (class "Default")
      (node (ref "U4") (pin "2") (pinfunction "2_D_SEL_2") (pintype "bidirectional"))
    )
    (net (code "166") (name "unconnected-(U4-3_TIMEPULSE-Pad3)") (class "Default")
      (node (ref "U4") (pin "3") (pinfunction "3_TIMEPULSE_3") (pintype "bidirectional"))
    )
    (net (code "167") (name "unconnected-(U4-4_EXTINT-Pad4)") (class "Default")
      (node (ref "U4") (pin "4") (pinfunction "4_EXTINT_4") (pintype "bidirectional"))
    )
    (net (code "168") (name "unconnected-(U4-5_USB_DM-Pad5)") (class "Default")
      (node (ref "U4") (pin "5") (pinfunction "5_USB_DM_5") (pintype "bidirectional"))
    )
    (net (code "169") (name "unconnected-(U4-6_USB_DP-Pad6)") (class "Default")
      (node (ref "U4") (pin "6") (pinfunction "6_USB_DP_6") (pintype "bidirectional"))
    )
    (net (code "170") (name "unconnected-(U4-8_RESET_N-Pad8)") (class "Default")
      (node (ref "U4") (pin "8") (pinfunction "8_RESET_N_8") (pintype "bidirectional"))
    )
    (net (code "171") (name "unconnected-(U4-14_LNA_EN{slash}RESERVED-Pad14)") (class "Default")
      (node (ref "U4") (pin "14") (pinfunction "14_LNA_EN/RESERVED_14") (pintype "bidirectional"))
    )
    (net (code "172") (name "unconnected-(U4-15_RESERVED-Pad15)") (class "Default")
      (node (ref "U4") (pin "15") (pinfunction "15_RESERVED_15") (pintype "bidirectional"))
    )
    (net (code "173") (name "unconnected-(U4-16_RESERVED-Pad16)") (class "Default")
      (node (ref "U4") (pin "16") (pinfunction "16_RESERVED_16") (pintype "bidirectional"))
    )
    (net (code "174") (name "unconnected-(U4-17_RESERVED-Pad17)") (class "Default")
      (node (ref "U4") (pin "17") (pinfunction "17_RESERVED_17") (pintype "bidirectional"))
    )
    (net (code "175") (name "unconnected-(U4-20_TXD{slash}SPI_MISO-Pad20)") (class "Default")
      (node (ref "U4") (pin "20") (pinfunction "20_TXD/SPI_MISO_20") (pintype "bidirectional"))
    )
    (net (code "176") (name "unconnected-(U4-21_RXD{slash}SPI_MOSI-Pad21)") (class "Default")
      (node (ref "U4") (pin "21") (pinfunction "21_RXD/SPI_MOSI_21") (pintype "bidirectional"))
    )
    (net (code "177") (name "unconnected-(U6-CAM1_DN2-Pad143)") (class "Default")
      (node (ref "U6") (pin "143") (pinfunction "CAM1_DN2_143") (pintype "bidirectional"))
    )
    (net (code "178") (name "unconnected-(U6-CAM1_DN3-Pad137)") (class "Default")
      (node (ref "U6") (pin "137") (pinfunction "CAM1_DN3_137") (pintype "bidirectional"))
    )
    (net (code "179") (name "unconnected-(U6-CAM1_DP2-Pad141)") (class "Default")
      (node (ref "U6") (pin "141") (pinfunction "CAM1_DP2_141") (pintype "bidirectional"))
    )
    (net (code "180") (name "unconnected-(U6-CAM1_DP3-Pad135)") (class "Default")
      (node (ref "U6") (pin "135") (pinfunction "CAM1_DP3_135") (pintype "bidirectional"))
    )
    (net (code "181") (name "unconnected-(U6-DSI0_CN-Pad105)") (class "Default")
      (node (ref "U6") (pin "105") (pinfunction "DSI0_CN_105") (pintype "bidirectional"))
    )
    (net (code "182") (name "unconnected-(U6-DSI0_CP-Pad107)") (class "Default")
      (node (ref "U6") (pin "107") (pinfunction "DSI0_CP_107") (pintype "bidirectional"))
    )
    (net (code "183") (name "unconnected-(U6-DSI0_DN0-Pad99)") (class "Default")
      (node (ref "U6") (pin "99") (pinfunction "DSI0_DN0_99") (pintype "bidirectional"))
    )
    (net (code "184") (name "unconnected-(U6-DSI0_DN1-Pad93)") (class "Default")
      (node (ref "U6") (pin "93") (pinfunction "DSI0_DN1_93") (pintype "bidirectional"))
    )
    (net (code "185") (name "unconnected-(U6-DSI0_DP0-Pad101)") (class "Default")
      (node (ref "U6") (pin "101") (pinfunction "DSI0_DP0_101") (pintype "bidirectional"))
    )
    (net (code "186") (name "unconnected-(U6-DSI0_DP1-Pad95)") (class "Default")
      (node (ref "U6") (pin "95") (pinfunction "DSI0_DP1_95") (pintype "bidirectional"))
    )
    (net (code "187") (name "unconnected-(U6-DSI1_CN-Pad102)") (class "Default")
      (node (ref "U6") (pin "102") (pinfunction "DSI1_CN_102") (pintype "bidirectional"))
    )
    (net (code "188") (name "unconnected-(U6-DSI1_CP-Pad100)") (class "Default")
      (node (ref "U6") (pin "100") (pinfunction "DSI1_CP_100") (pintype "bidirectional"))
    )
    (net (code "189") (name "unconnected-(U6-DSI1_DN0-Pad96)") (class "Default")
      (node (ref "U6") (pin "96") (pinfunction "DSI1_DN0_96") (pintype "bidirectional"))
    )
    (net (code "190") (name "unconnected-(U6-DSI1_DN1-Pad120)") (class "Default")
      (node (ref "U6") (pin "120") (pinfunction "DSI1_DN1_120") (pintype "bidirectional"))
    )
    (net (code "191") (name "unconnected-(U6-DSI1_DN2-Pad114)") (class "Default")
      (node (ref "U6") (pin "114") (pinfunction "DSI1_DN2_114") (pintype "bidirectional"))
    )
    (net (code "192") (name "unconnected-(U6-DSI1_DN3-Pad108)") (class "Default")
      (node (ref "U6") (pin "108") (pinfunction "DSI1_DN3_108") (pintype "bidirectional"))
    )
    (net (code "193") (name "unconnected-(U6-DSI1_DP0-Pad94)") (class "Default")
      (node (ref "U6") (pin "94") (pinfunction "DSI1_DP0_94") (pintype "bidirectional"))
    )
    (net (code "194") (name "unconnected-(U6-DSI1_DP1-Pad118)") (class "Default")
      (node (ref "U6") (pin "118") (pinfunction "DSI1_DP1_118") (pintype "bidirectional"))
    )
    (net (code "195") (name "unconnected-(U6-DSI1_DP2-Pad112)") (class "Default")
      (node (ref "U6") (pin "112") (pinfunction "DSI1_DP2_112") (pintype "bidirectional"))
    )
    (net (code "196") (name "unconnected-(U6-DSI1_DP3-Pad106)") (class "Default")
      (node (ref "U6") (pin "106") (pinfunction "DSI1_DP3_106") (pintype "bidirectional"))
    )
    (net (code "197") (name "unconnected-(U6-EMMC_EN_N_1V8-Pad90)") (class "Default")
      (node (ref "U6") (pin "90") (pinfunction "EMMC_EN_N_1V8_90") (pintype "bidirectional"))
    )
    (net (code "198") (name "unconnected-(U6-GPIO45-Pad84)") (class "Default")
      (node (ref "U6") (pin "84") (pinfunction "GPIO45_84") (pintype "bidirectional"))
    )
    (net (code "199") (name "unconnected-(U6-HDMI_CEC-Pad171)") (class "Default")
      (node (ref "U6") (pin "171") (pinfunction "HDMI_CEC_171") (pintype "bidirectional"))
    )
    (net (code "200") (name "unconnected-(U6-HDMI_CK_N-Pad111)") (class "Default")
      (node (ref "U6") (pin "111") (pinfunction "HDMI_CK_N_111") (pintype "bidirectional"))
    )
    (net (code "201") (name "unconnected-(U6-HDMI_CK_P-Pad113)") (class "Default")
      (node (ref "U6") (pin "113") (pinfunction "HDMI_CK_P_113") (pintype "bidirectional"))
    )
    (net (code "202") (name "unconnected-(U6-HDMI_D0_N-Pad117)") (class "Default")
      (node (ref "U6") (pin "117") (pinfunction "HDMI_D0_N_117") (pintype "bidirectional"))
    )
    (net (code "203") (name "unconnected-(U6-HDMI_D0_P-Pad119)") (class "Default")
      (node (ref "U6") (pin "119") (pinfunction "HDMI_D0_P_119") (pintype "bidirectional"))
    )
    (net (code "204") (name "unconnected-(U6-HDMI_D1_N-Pad123)") (class "Default")
      (node (ref "U6") (pin "123") (pinfunction "HDMI_D1_N_123") (pintype "bidirectional"))
    )
    (net (code "205") (name "unconnected-(U6-HDMI_D1_P-Pad125)") (class "Default")
      (node (ref "U6") (pin "125") (pinfunction "HDMI_D1_P_125") (pintype "bidirectional"))
    )
    (net (code "206") (name "unconnected-(U6-HDMI_D2_N-Pad129)") (class "Default")
      (node (ref "U6") (pin "129") (pinfunction "HDMI_D2_N_129") (pintype "bidirectional"))
    )
    (net (code "207") (name "unconnected-(U6-HDMI_D2_P-Pad131)") (class "Default")
      (node (ref "U6") (pin "131") (pinfunction "HDMI_D2_P_131") (pintype "bidirectional"))
    )
    (net (code "208") (name "unconnected-(U6-HDMI_HPD_N_1V8-Pad88)") (class "Default")
      (node (ref "U6") (pin "88") (pinfunction "HDMI_HPD_N_1V8_88") (pintype "bidirectional"))
    )
    (net (code "209") (name "unconnected-(U6-HDMI_SCL-Pad175)") (class "Default")
      (node (ref "U6") (pin "175") (pinfunction "HDMI_SCL_175") (pintype "bidirectional"))
    )
    (net (code "210") (name "unconnected-(U6-HDMI_SDA-Pad173)") (class "Default")
      (node (ref "U6") (pin "173") (pinfunction "HDMI_SDA_173") (pintype "bidirectional"))
    )
    (net (code "211") (name "unconnected-(U6-NC-Pad124)") (class "Default")
      (node (ref "U6") (pin "124") (pinfunction "NC_124") (pintype "bidirectional"))
    )
    (net (code "212") (name "unconnected-(U6-NC-Pad126)") (class "Default")
      (node (ref "U6") (pin "126") (pinfunction "NC_126") (pintype "bidirectional"))
    )
    (net (code "213") (name "unconnected-(U6-NC-Pad128)") (class "Default")
      (node (ref "U6") (pin "128") (pinfunction "NC_128") (pintype "bidirectional"))
    )
    (net (code "214") (name "unconnected-(U6-NC-Pad130)") (class "Default")
      (node (ref "U6") (pin "130") (pinfunction "NC_130") (pintype "bidirectional"))
    )
    (net (code "215") (name "unconnected-(U6-NC-Pad132)") (class "Default")
      (node (ref "U6") (pin "132") (pinfunction "NC_132") (pintype "bidirectional"))
    )
    (net (code "216") (name "unconnected-(U6-NC-Pad154)") (class "Default")
      (node (ref "U6") (pin "154") (pinfunction "NC_154") (pintype "bidirectional"))
    )
    (net (code "217") (name "unconnected-(U6-NC-Pad156)") (class "Default")
      (node (ref "U6") (pin "156") (pinfunction "NC_156") (pintype "bidirectional"))
    )
    (net (code "218") (name "unconnected-(U6-NC-Pad158)") (class "Default")
      (node (ref "U6") (pin "158") (pinfunction "NC_158") (pintype "bidirectional"))
    )
    (net (code "219") (name "unconnected-(U6-NC-Pad160)") (class "Default")
      (node (ref "U6") (pin "160") (pinfunction "NC_160") (pintype "bidirectional"))
    )
    (net (code "220") (name "unconnected-(U6-NC-Pad162)") (class "Default")
      (node (ref "U6") (pin "162") (pinfunction "NC_162") (pintype "bidirectional"))
    )
    (net (code "221") (name "unconnected-(U6-RUN-Pad177)") (class "Default")
      (node (ref "U6") (pin "177") (pinfunction "RUN_177") (pintype "bidirectional"))
    )
    (net (code "222") (name "unconnected-(U6-TVDAC-Pad166)") (class "Default")
      (node (ref "U6") (pin "166") (pinfunction "TVDAC_166") (pintype "bidirectional"))
    )
    (net (code "223") (name "unconnected-(U6-VC_TCK-Pad180)") (class "Default")
      (node (ref "U6") (pin "180") (pinfunction "VC_TCK_180") (pintype "bidirectional"))
    )
    (net (code "224") (name "unconnected-(U6-VC_TDI-Pad174)") (class "Default")
      (node (ref "U6") (pin "174") (pinfunction "VC_TDI_174") (pintype "bidirectional"))
    )
    (net (code "225") (name "unconnected-(U6-VC_TDO-Pad178)") (class "Default")
      (node (ref "U6") (pin "178") (pinfunction "VC_TDO_178") (pintype "bidirectional"))
    )
    (net (code "226") (name "unconnected-(U6-VC_TMS-Pad176)") (class "Default")
      (node (ref "U6") (pin "176") (pinfunction "VC_TMS_176") (pintype "bidirectional"))
    )
    (net (code "227") (name "unconnected-(U6-VC_TRST_N-Pad172)") (class "Default")
      (node (ref "U6") (pin "172") (pinfunction "VC_TRST_N_172") (pintype "bidirectional"))
    )
    (net (code "228") (name "unconnected-(U6-VDAC-Pad189)") (class "Default")
      (node (ref "U6") (pin "189") (pinfunction "VDAC_189") (pintype "bidirectional"))
    )
    (net (code "229") (name "unconnected-(U6-VDAC-Pad190)") (class "Default")
      (node (ref "U6") (pin "190") (pinfunction "VDAC_190") (pintype "bidirectional"))
    )
    (net (code "230") (name "unconnected-(U6-VDD_CORE-Pad179)") (class "Default")
      (node (ref "U6") (pin "179") (pinfunction "VDD_CORE_179") (pintype "bidirectional"))
    )
    (net (code "231") (name "unconnected-(U7-CTS-Pad31)") (class "Default")
      (node (ref "U7") (pin "31") (pinfunction "CTS_31") (pintype "bidirectional"))
    )
    (net (code "232") (name "unconnected-(U7-DSR-Pad30)") (class "Default")
      (node (ref "U7") (pin "30") (pinfunction "DSR_30") (pintype "bidirectional"))
    )
    (net (code "233") (name "unconnected-(U7-DTR-Pad32)") (class "Default")
      (node (ref "U7") (pin "32") (pinfunction "DTR_32") (pintype "bidirectional"))
    )
    (net (code "234") (name "unconnected-(U7-LED1-Pad20)") (class "Default")
      (node (ref "U7") (pin "20") (pinfunction "LED1_20") (pintype "bidirectional"))
    )
    (net (code "235") (name "unconnected-(U7-LED2-Pad21)") (class "Default")
      (node (ref "U7") (pin "21") (pinfunction "LED2_21") (pintype "bidirectional"))
    )
    (net (code "236") (name "unconnected-(U7-LED3-Pad22)") (class "Default")
      (node (ref "U7") (pin "22") (pinfunction "LED3_22") (pintype "bidirectional"))
    )
    (net (code "237") (name "unconnected-(U7-LEDRX-Pad23)") (class "Default")
      (node (ref "U7") (pin "23") (pinfunction "LEDRX_23") (pintype "bidirectional"))
    )
    (net (code "238") (name "unconnected-(U7-LEDTX-Pad24)") (class "Default")
      (node (ref "U7") (pin "24") (pinfunction "LEDTX_24") (pintype "bidirectional"))
    )
    (net (code "239") (name "unconnected-(U7-LINK_LED_WAN-Pad49)") (class "Default")
      (node (ref "U7") (pin "49") (pinfunction "LINK_LED_WAN_49") (pintype "bidirectional"))
    )
    (net (code "240") (name "unconnected-(U7-Pad2)") (class "Default")
      (node (ref "U7") (pin "2") (pinfunction "2_2") (pintype "bidirectional"))
    )
    (net (code "241") (name "unconnected-(U7-Pad3)") (class "Default")
      (node (ref "U7") (pin "3") (pinfunction "3_3") (pintype "bidirectional"))
    )
    (net (code "242") (name "unconnected-(U7-Pad4)") (class "Default")
      (node (ref "U7") (pin "4") (pinfunction "4_4") (pintype "bidirectional"))
    )
    (net (code "243") (name "unconnected-(U7-Pad5)") (class "Default")
      (node (ref "U7") (pin "5") (pinfunction "5_5") (pintype "bidirectional"))
    )
    (net (code "244") (name "unconnected-(U7-Pad6)") (class "Default")
      (node (ref "U7") (pin "6") (pinfunction "6_6") (pintype "bidirectional"))
    )
    (net (code "245") (name "unconnected-(U7-Pad7)") (class "Default")
      (node (ref "U7") (pin "7") (pinfunction "7_7") (pintype "bidirectional"))
    )
    (net (code "246") (name "unconnected-(U7-Pad8)") (class "Default")
      (node (ref "U7") (pin "8") (pinfunction "8_8") (pintype "bidirectional"))
    )
    (net (code "247") (name "unconnected-(U7-Pad9)") (class "Default")
      (node (ref "U7") (pin "9") (pinfunction "9_9") (pintype "bidirectional"))
    )
    (net (code "248") (name "unconnected-(U7-Pad10)") (class "Default")
      (node (ref "U7") (pin "10") (pinfunction "10_10") (pintype "bidirectional"))
    )
    (net (code "249") (name "unconnected-(U7-Pad12)") (class "Default")
      (node (ref "U7") (pin "12") (pinfunction "12_12") (pintype "bidirectional"))
    )
    (net (code "250") (name "unconnected-(U7-Pad27)") (class "Default")
      (node (ref "U7") (pin "27") (pinfunction "27_27") (pintype "bidirectional"))
    )
    (net (code "251") (name "unconnected-(U7-Pad33)") (class "Default")
      (node (ref "U7") (pin "33") (pinfunction "33_33") (pintype "bidirectional"))
    )
    (net (code "252") (name "unconnected-(U7-Pad35)") (class "Default")
      (node (ref "U7") (pin "35") (pinfunction "35_35") (pintype "bidirectional"))
    )
    (net (code "253") (name "unconnected-(U7-Pad36)") (class "Default")
      (node (ref "U7") (pin "36") (pinfunction "36_36") (pintype "bidirectional"))
    )
    (net (code "254") (name "unconnected-(U7-Pad37)") (class "Default")
      (node (ref "U7") (pin "37") (pinfunction "37_37") (pintype "bidirectional"))
    )
    (net (code "255") (name "unconnected-(U7-Pad38)") (class "Default")
      (node (ref "U7") (pin "38") (pinfunction "38_38") (pintype "bidirectional"))
    )
    (net (code "256") (name "unconnected-(U7-Pad45)") (class "Default")
      (node (ref "U7") (pin "45") (pinfunction "45_45") (pintype "bidirectional"))
    )
    (net (code "257") (name "unconnected-(U7-Pad46)") (class "Default")
      (node (ref "U7") (pin "46") (pinfunction "46_46") (pintype "bidirectional"))
    )
    (net (code "258") (name "unconnected-(U7-Pad47)") (class "Default")
      (node (ref "U7") (pin "47") (pinfunction "47_47") (pintype "bidirectional"))
    )
    (net (code "259") (name "unconnected-(U7-Pad48)") (class "Default")
      (node (ref "U7") (pin "48") (pinfunction "48_48") (pintype "bidirectional"))
    )
    (net (code "260") (name "unconnected-(U7-Pad50)") (class "Default")
      (node (ref "U7") (pin "50") (pinfunction "50_50") (pintype "bidirectional"))
    )
    (net (code "261") (name "unconnected-(U7-Pad51)") (class "Default")
      (node (ref "U7") (pin "51") (pinfunction "51_51") (pintype "bidirectional"))
    )
    (net (code "262") (name "unconnected-(U7-Pad52)") (class "Default")
      (node (ref "U7") (pin "52") (pinfunction "52_52") (pintype "bidirectional"))
    )
    (net (code "263") (name "unconnected-(U7-Pad53)") (class "Default")
      (node (ref "U7") (pin "53") (pinfunction "53_53") (pintype "bidirectional"))
    )
    (net (code "264") (name "unconnected-(U7-Pad54)") (class "Default")
      (node (ref "U7") (pin "54") (pinfunction "54_54") (pintype "bidirectional"))
    )
    (net (code "265") (name "unconnected-(U7-Pad59)") (class "Default")
      (node (ref "U7") (pin "59") (pinfunction "59_59") (pintype "bidirectional"))
    )
    (net (code "266") (name "unconnected-(U7-RESET-Pad16)") (class "Default")
      (node (ref "U7") (pin "16") (pinfunction "RESET_16") (pintype "bidirectional"))
    )
    (net (code "267") (name "unconnected-(U7-RTS-Pad34)") (class "Default")
      (node (ref "U7") (pin "34") (pinfunction "RTS_34") (pintype "bidirectional"))
    )
    (net (code "268") (name "unconnected-(U7-RX-Pad28)") (class "Default")
      (node (ref "U7") (pin "28") (pinfunction "RX_28") (pintype "bidirectional"))
    )
    (net (code "269") (name "unconnected-(U7-RX_N_WAN-Pad41)") (class "Default")
      (node (ref "U7") (pin "41") (pinfunction "RX_N_WAN_41") (pintype "bidirectional"))
    )
    (net (code "270") (name "unconnected-(U7-RX_P_WAN-Pad42)") (class "Default")
      (node (ref "U7") (pin "42") (pinfunction "RX_P_WAN_42") (pintype "bidirectional"))
    )
    (net (code "271") (name "unconnected-(U7-TX-Pad29)") (class "Default")
      (node (ref "U7") (pin "29") (pinfunction "TX_29") (pintype "bidirectional"))
    )
    (net (code "272") (name "unconnected-(U7-TX_N_WAN-Pad43)") (class "Default")
      (node (ref "U7") (pin "43") (pinfunction "TX_N_WAN_43") (pintype "bidirectional"))
    )
    (net (code "273") (name "unconnected-(U7-TX_P_WAN-Pad44)") (class "Default")
      (node (ref "U7") (pin "44") (pinfunction "TX_P_WAN_44") (pintype "bidirectional"))
    )
    (net (code "274") (name "unconnected-(U7-USB_D+-Pad18)") (class "Default")
      (node (ref "U7") (pin "18") (pinfunction "USB_D+_18") (pintype "bidirectional"))
    )
    (net (code "275") (name "unconnected-(U7-USB_D--Pad19)") (class "Default")
      (node (ref "U7") (pin "19") (pinfunction "USB_D-_19") (pintype "bidirectional"))
    )
    (net (code "276") (name "unconnected-(U7-USB_MODE-Pad14)") (class "Default")
      (node (ref "U7") (pin "14") (pinfunction "USB_MODE_14") (pintype "bidirectional"))
    )
    (net (code "277") (name "unconnected-(U10-PA0-Pad14)") (class "Default")
      (node (ref "U10") (pin "14") (pinfunction "PA0_14") (pintype "bidirectional"))
    )
    (net (code "278") (name "unconnected-(U10-PA1-Pad15)") (class "Default")
      (node (ref "U10") (pin "15") (pinfunction "PA1_15") (pintype "bidirectional"))
    )
    (net (code "279") (name "unconnected-(U10-PA2-Pad16)") (class "Default")
      (node (ref "U10") (pin "16") (pinfunction "PA2_16") (pintype "bidirectional"))
    )
    (net (code "280") (name "unconnected-(U10-PA3-Pad17)") (class "Default")
      (node (ref "U10") (pin "17") (pinfunction "PA3_17") (pintype "bidirectional"))
    )
    (net (code "281") (name "unconnected-(U10-PA8-Pad41)") (class "Default")
      (node (ref "U10") (pin "41") (pinfunction "PA8_41") (pintype "bidirectional"))
    )
    (net (code "282") (name "unconnected-(U10-PA9-Pad42)") (class "Default")
      (node (ref "U10") (pin "42") (pinfunction "PA9_42") (pintype "bidirectional"))
    )
    (net (code "283") (name "unconnected-(U10-PA10-Pad43)") (class "Default")
      (node (ref "U10") (pin "43") (pinfunction "PA10_43") (pintype "bidirectional"))
    )
    (net (code "284") (name "unconnected-(U10-PA11-Pad44)") (class "Default")
      (node (ref "U10") (pin "44") (pinfunction "PA11_44") (pintype "bidirectional"))
    )
    (net (code "285") (name "unconnected-(U10-PA12-Pad45)") (class "Default")
      (node (ref "U10") (pin "45") (pinfunction "PA12_45") (pintype "bidirectional"))
    )
    (net (code "286") (name "unconnected-(U10-PA15-Pad50)") (class "Default")
      (node (ref "U10") (pin "50") (pinfunction "PA15_50") (pintype "bidirectional"))
    )
    (net (code "287") (name "unconnected-(U10-PB2-Pad28)") (class "Default")
      (node (ref "U10") (pin "28") (pinfunction "PB2_28") (pintype "bidirectional"))
    )
    (net (code "288") (name "unconnected-(U10-PB3-Pad55)") (class "Default")
      (node (ref "U10") (pin "55") (pinfunction "PB3_55") (pintype "bidirectional"))
    )
    (net (code "289") (name "unconnected-(U10-PB4-Pad56)") (class "Default")
      (node (ref "U10") (pin "56") (pinfunction "PB4_56") (pintype "bidirectional"))
    )
    (net (code "290") (name "unconnected-(U10-PB5-Pad57)") (class "Default")
      (node (ref "U10") (pin "57") (pinfunction "PB5_57") (pintype "bidirectional"))
    )
    (net (code "291") (name "unconnected-(U10-PB6-Pad58)") (class "Default")
      (node (ref "U10") (pin "58") (pinfunction "PB6_58") (pintype "bidirectional"))
    )
    (net (code "292") (name "unconnected-(U10-PB10-Pad29)") (class "Default")
      (node (ref "U10") (pin "29") (pinfunction "PB10_29") (pintype "bidirectional"))
    )
    (net (code "293") (name "unconnected-(U10-PB12-Pad33)") (class "Default")
      (node (ref "U10") (pin "33") (pinfunction "PB12_33") (pintype "bidirectional"))
    )
    (net (code "294") (name "unconnected-(U10-PB13-Pad34)") (class "Default")
      (node (ref "U10") (pin "34") (pinfunction "PB13_34") (pintype "bidirectional"))
    )
    (net (code "295") (name "unconnected-(U10-PB14-Pad35)") (class "Default")
      (node (ref "U10") (pin "35") (pinfunction "PB14_35") (pintype "bidirectional"))
    )
    (net (code "296") (name "unconnected-(U10-PB15-Pad36)") (class "Default")
      (node (ref "U10") (pin "36") (pinfunction "PB15_36") (pintype "bidirectional"))
    )
    (net (code "297") (name "unconnected-(U10-PC0-Pad8)") (class "Default")
      (node (ref "U10") (pin "8") (pinfunction "PC0_8") (pintype "bidirectional"))
    )
    (net (code "298") (name "unconnected-(U10-PC1-Pad9)") (class "Default")
      (node (ref "U10") (pin "9") (pinfunction "PC1_9") (pintype "bidirectional"))
    )
    (net (code "299") (name "unconnected-(U10-PC2-Pad10)") (class "Default")
      (node (ref "U10") (pin "10") (pinfunction "PC2_10") (pintype "bidirectional"))
    )
    (net (code "300") (name "unconnected-(U10-PC3-Pad11)") (class "Default")
      (node (ref "U10") (pin "11") (pinfunction "PC3_11") (pintype "bidirectional"))
    )
    (net (code "301") (name "unconnected-(U10-PC6-Pad37)") (class "Default")
      (node (ref "U10") (pin "37") (pinfunction "PC6_37") (pintype "bidirectional"))
    )
    (net (code "302") (name "unconnected-(U10-PC7-Pad38)") (class "Default")
      (node (ref "U10") (pin "38") (pinfunction "PC7_38") (pintype "bidirectional"))
    )
    (net (code "303") (name "unconnected-(U10-PC8-Pad39)") (class "Default")
      (node (ref "U10") (pin "39") (pinfunction "PC8_39") (pintype "bidirectional"))
    )
    (net (code "304") (name "unconnected-(U10-PC9-Pad40)") (class "Default")
      (node (ref "U10") (pin "40") (pinfunction "PC9_40") (pintype "bidirectional"))
    )
    (net (code "305") (name "unconnected-(U10-PC10-Pad51)") (class "Default")
      (node (ref "U10") (pin "51") (pinfunction "PC10_51") (pintype "bidirectional"))
    )
    (net (code "306") (name "unconnected-(U10-PC11-Pad52)") (class "Default")
      (node (ref "U10") (pin "52") (pinfunction "PC11_52") (pintype "bidirectional"))
    )
    (net (code "307") (name "unconnected-(U10-PC12-Pad53)") (class "Default")
      (node (ref "U10") (pin "53") (pinfunction "PC12_53") (pintype "bidirectional"))
    )
    (net (code "308") (name "unconnected-(U10-PC13-Pad2)") (class "Default")
      (node (ref "U10") (pin "2") (pinfunction "PC13_2") (pintype "bidirectional"))
    )
    (net (code "309") (name "unconnected-(U10-PC14-Pad3)") (class "Default")
      (node (ref "U10") (pin "3") (pinfunction "PC14_3") (pintype "bidirectional"))
    )
    (net (code "310") (name "unconnected-(U10-PC15-Pad4)") (class "Default")
      (node (ref "U10") (pin "4") (pinfunction "PC15_4") (pintype "bidirectional"))
    )
    (net (code "311") (name "unconnected-(U10-PD2-Pad54)") (class "Default")
      (node (ref "U10") (pin "54") (pinfunction "PD2_54") (pintype "bidirectional"))
    )
    (net (code "312") (name "unconnected-(U10-PH0-OSC_IN-Pad5)") (class "Default")
      (node (ref "U10") (pin "5") (pinfunction "PH0-OSC_IN_5") (pintype "bidirectional"))
    )
    (net (code "313") (name "unconnected-(U10-PH1-OSC_OUT-Pad6)") (class "Default")
      (node (ref "U10") (pin "6") (pinfunction "PH1-OSC_OUT_6") (pintype "bidirectional"))
    )
    (net (code "314") (name "unconnected-(U11-PadADC)") (class "Default")
      (node (ref "U11") (pin "ADC") (pinfunction "ADC_ADC") (pintype "bidirectional"))
    )
    (net (code "315") (name "unconnected-(U11-PadGPIO0)") (class "Default")
      (node (ref "U11") (pin "GPIO0") (pinfunction "GPIO0_GPIO0") (pintype "bidirectional"))
    )
    (net (code "316") (name "unconnected-(U11-PadGPIO2)") (class "Default")
      (node (ref "U11") (pin "GPIO2") (pinfunction "GPIO2_GPIO2") (pintype "bidirectional"))
    )
    (net (code "317") (name "unconnected-(U11-PadGPIO5)") (class "Default")
      (node (ref "U11") (pin "GPIO5") (pinfunction "GPIO5_GPIO5") (pintype "bidirectional"))
    )
    (net (code "318") (name "unconnected-(U11-PadGPIO12)") (class "Default")
      (node (ref "U11") (pin "GPIO12") (pinfunction "GPIO12_GPIO12") (pintype "bidirectional"))
    )
    (net (code "319") (name "unconnected-(U11-PadGPIO13)") (class "Default")
      (node (ref "U11") (pin "GPIO13") (pinfunction "GPIO13_GPIO13") (pintype "bidirectional"))
    )
    (net (code "320") (name "unconnected-(U11-PadGPIO14)") (class "Default")
      (node (ref "U11") (pin "GPIO14") (pinfunction "GPIO14_GPIO14") (pintype "bidirectional"))
    )
    (net (code "321") (name "unconnected-(U11-PadGPIO15)") (class "Default")
      (node (ref "U11") (pin "GPIO15") (pinfunction "GPIO15_GPIO15") (pintype "bidirectional"))
    )
    (net (code "322") (name "unconnected-(U11-PadGPIO16)") (class "Default")
      (node (ref "U11") (pin "GPIO16") (pinfunction "GPIO16_GPIO16") (pintype "bidirectional"))
    )
    (net (code "323") (name "unconnected-(U11-PadRESET)") (class "Default")
      (node (ref "U11") (pin "RESET") (pinfunction "RESET_RESET") (pintype "bidirectional"))
    )
    (net (code "324") (name "unconnected-(U11-RX-PadRXD0)") (class "Default")
      (node (ref "U11") (pin "RXD0") (pinfunction "RX_RXD0") (pintype "bidirectional"))
    )
    (net (code "325") (name "unconnected-(U11-TX-PadTXD0)") (class "Default")
      (node (ref "U11") (pin "TXD0") (pinfunction "TX_TXD0") (pintype "bidirectional"))
    )
  )
)
